# preAutoRoute1.net
KiCad netlist of a schematic drawn in EAGLE
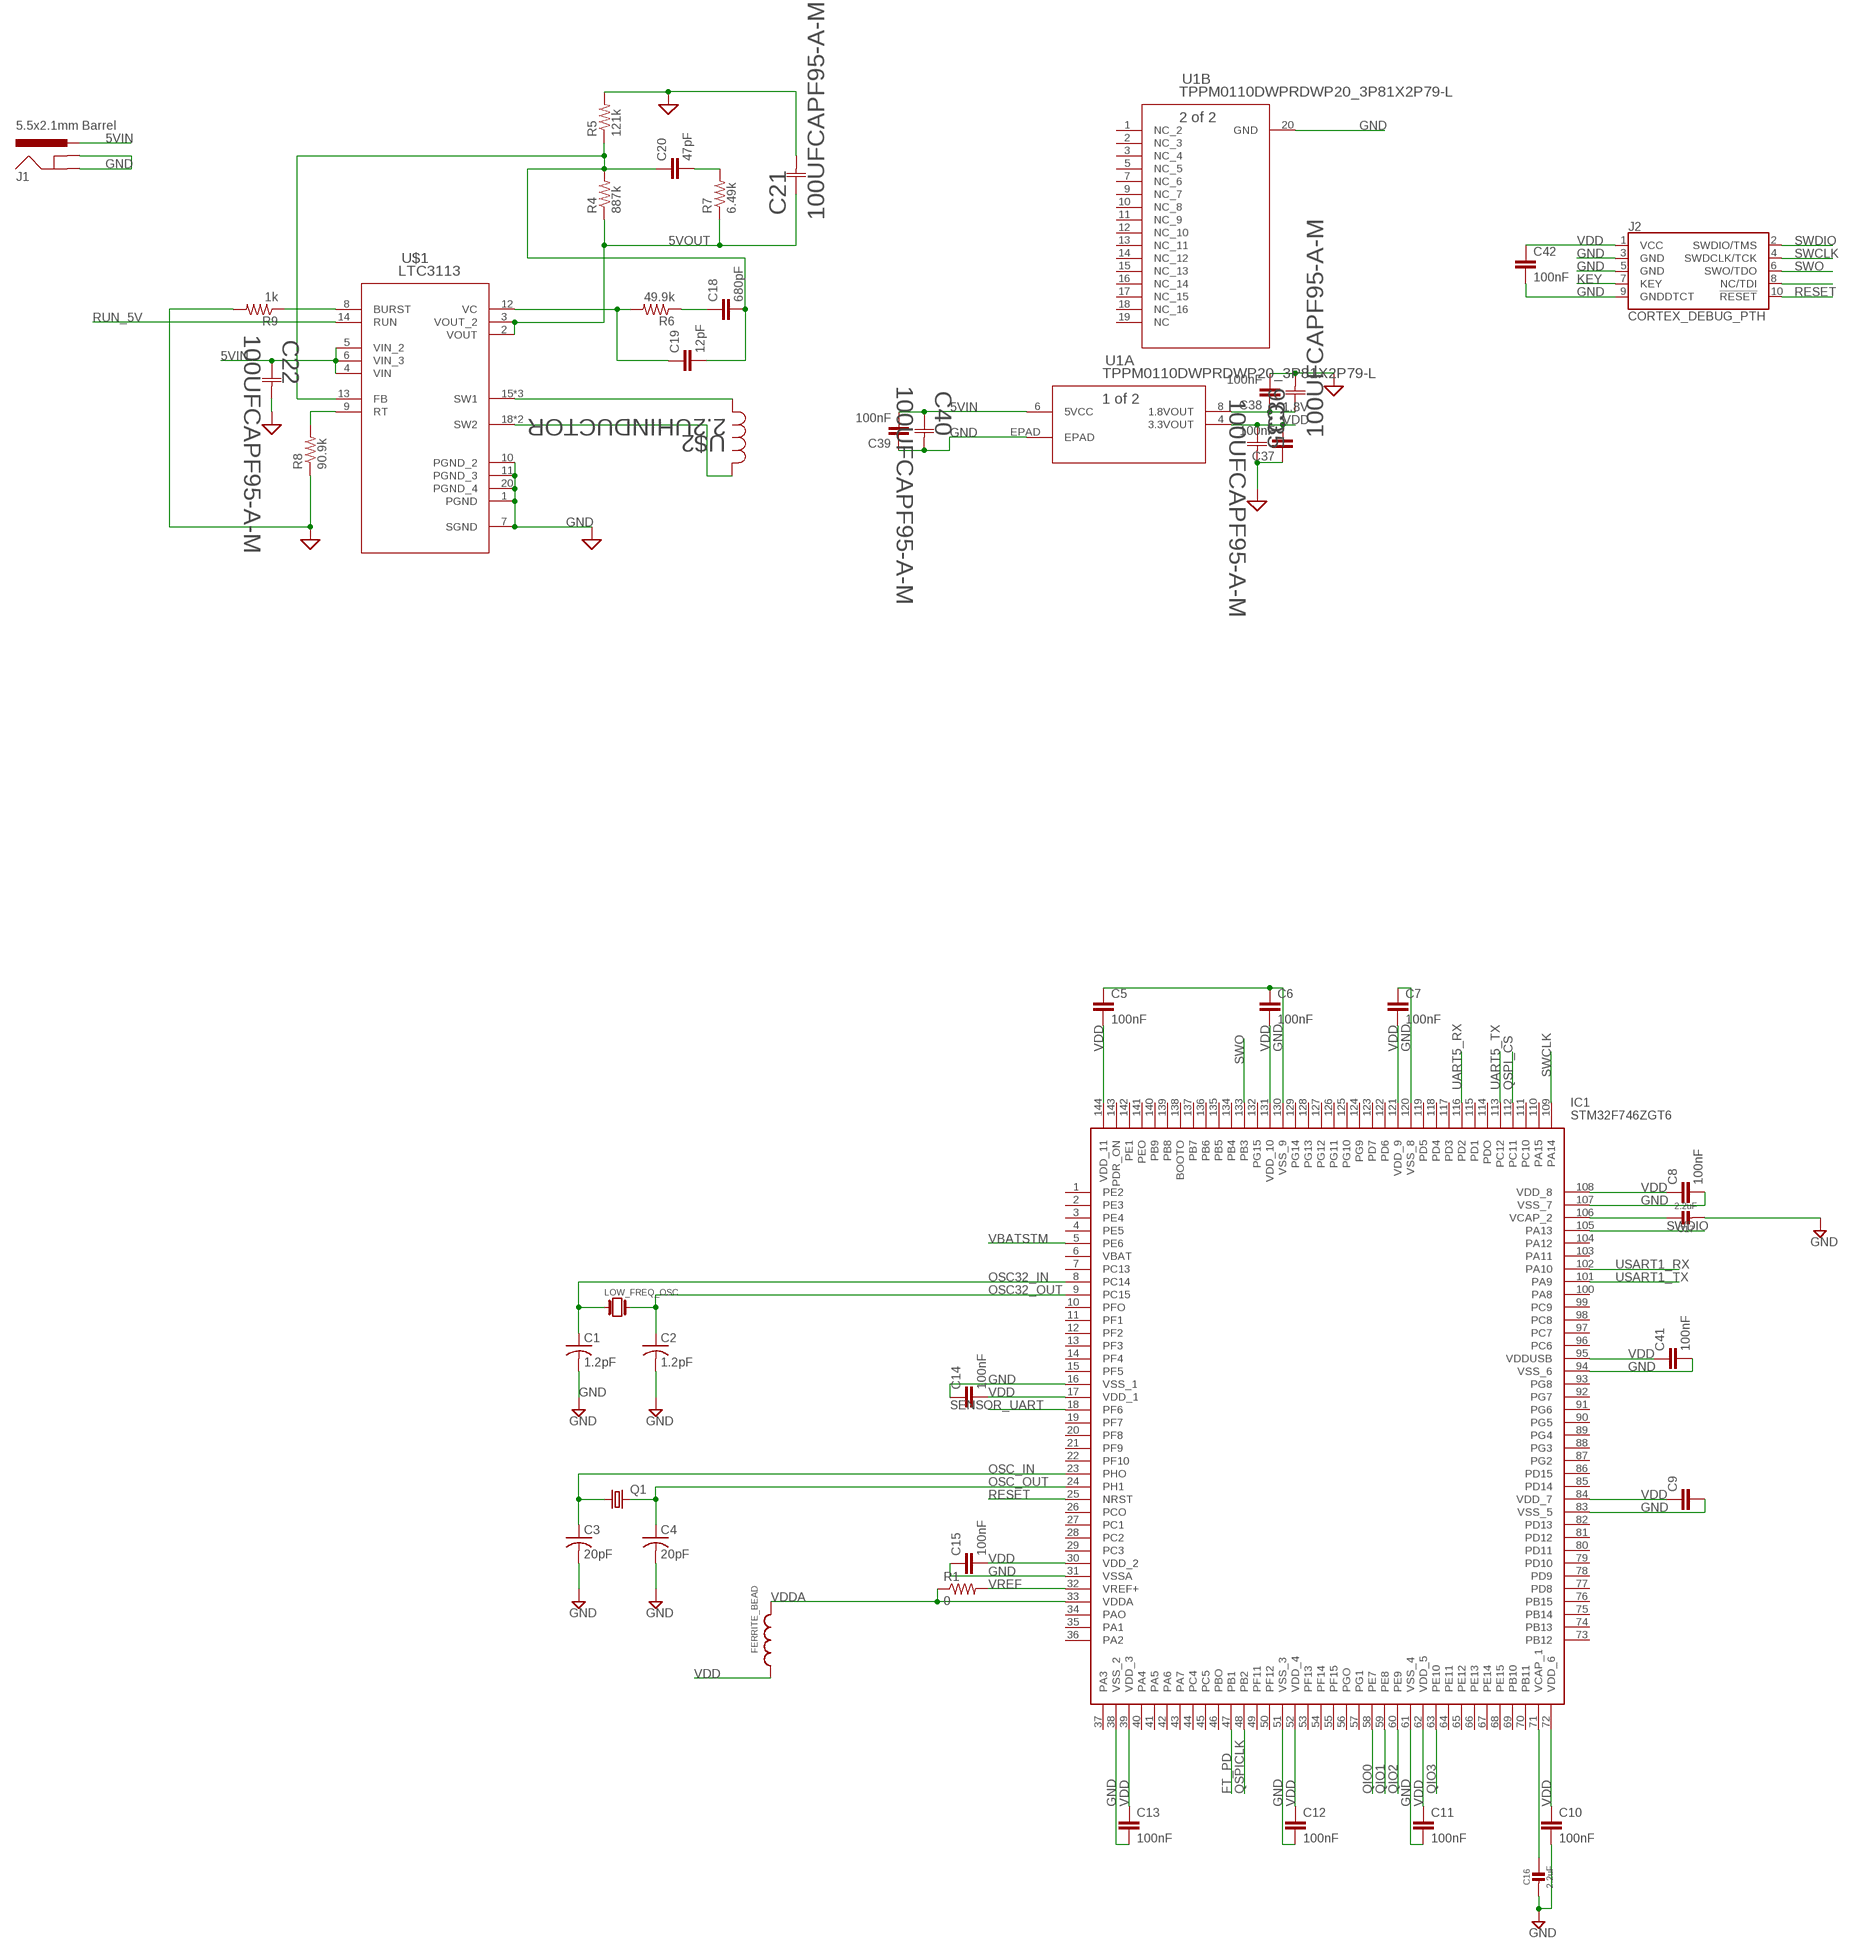
[diagram p0: schematic, sheet 1, part 1 of 2]
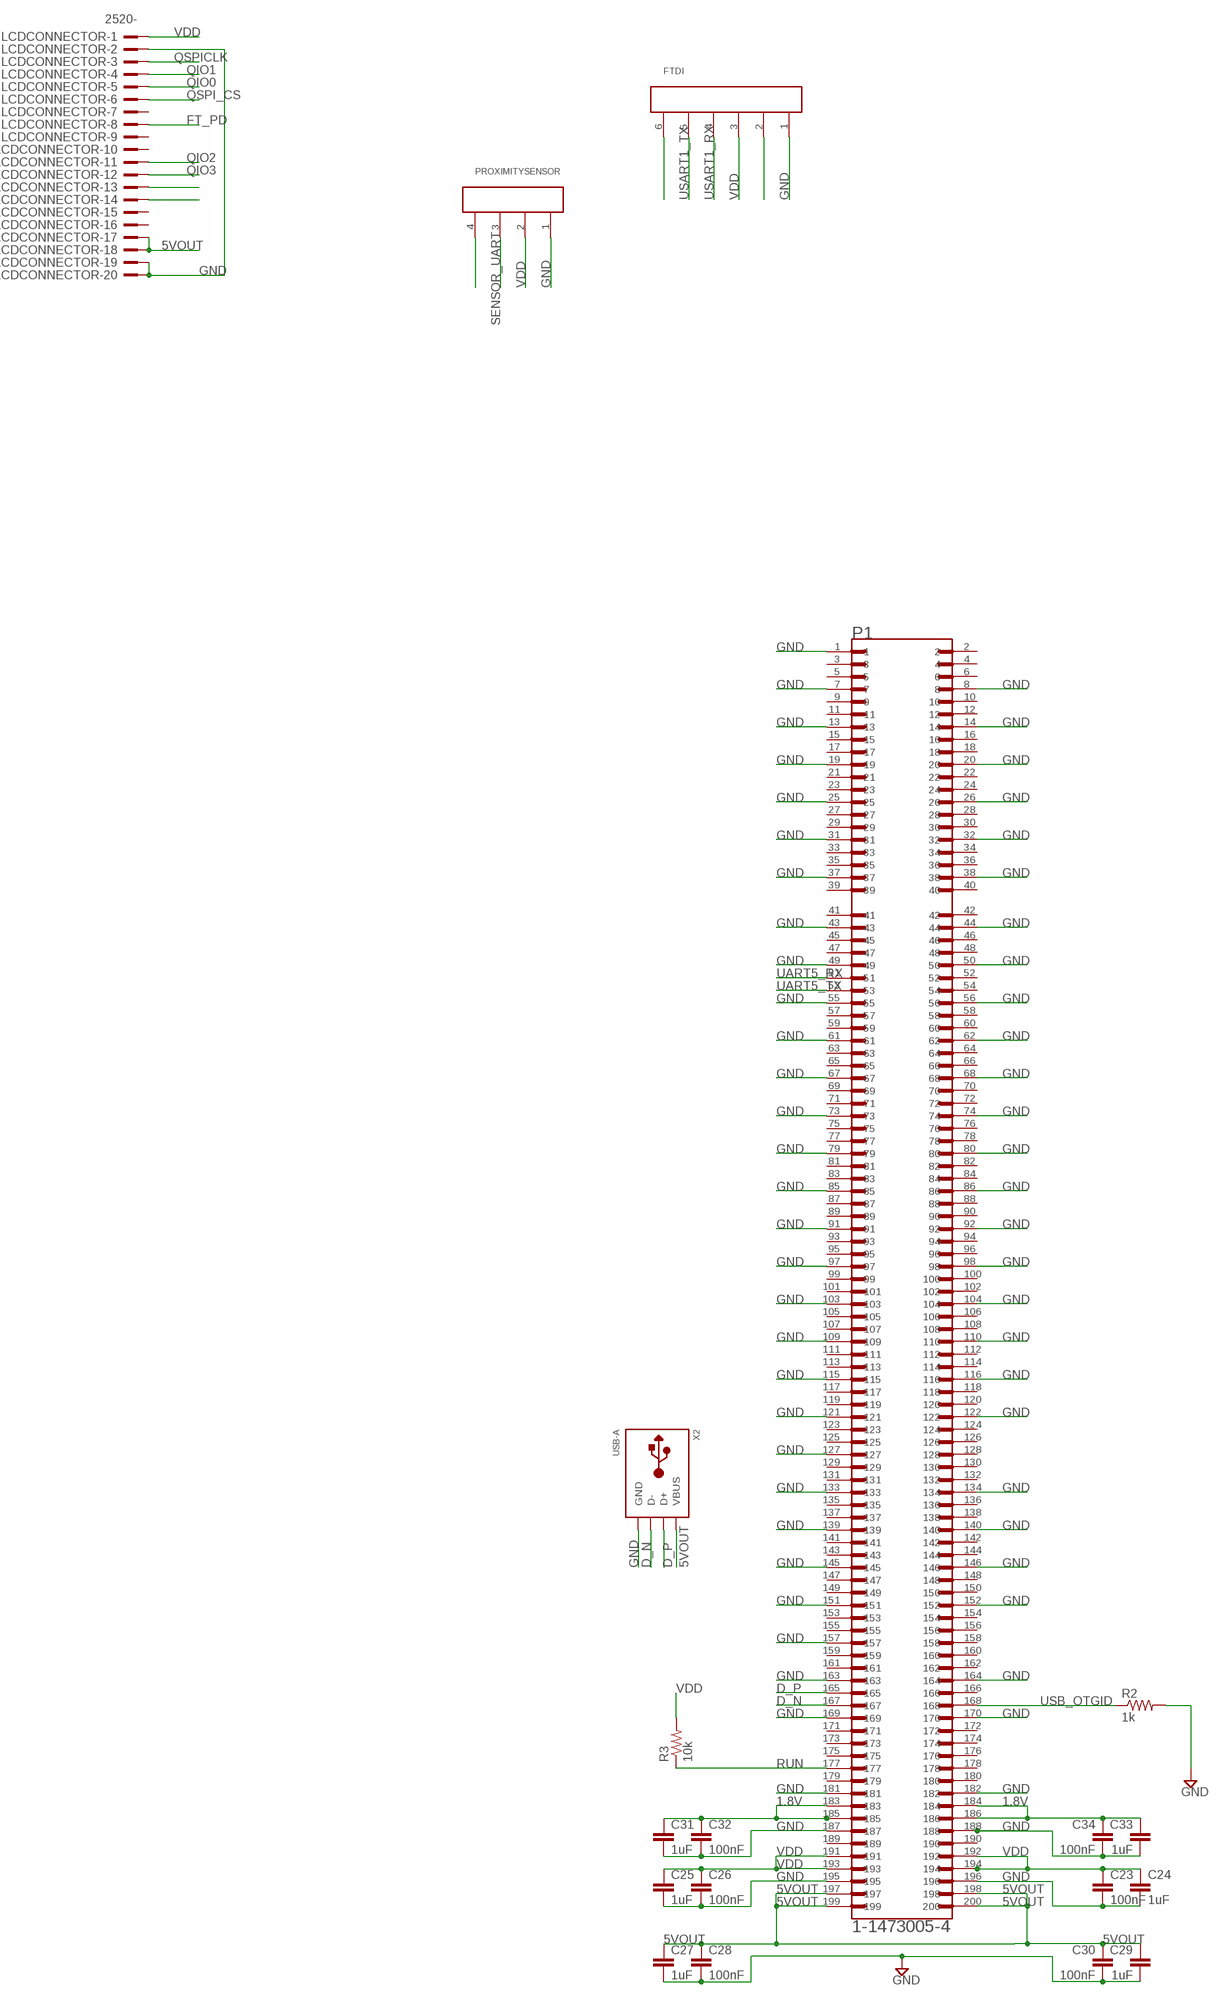
[diagram p1: schematic, sheet 1, part 2 of 2]

(export (version "E")
  (design (tool "Eeschema 10.0.6"))
  (components
    (comp (ref "C1")
      (value "1.2pF")
      (footprint "eagle-import:C0805")
      (libsource (lib "eagle-import") (part "C-USC0805"))
    )
    (comp (ref "C2")
      (value "1.2pF")
      (footprint "eagle-import:C0805")
      (libsource (lib "eagle-import") (part "C-USC0805"))
    )
    (comp (ref "C3")
      (value "20pF")
      (footprint "eagle-import:C0805")
      (libsource (lib "eagle-import") (part "C-USC0805"))
    )
    (comp (ref "C4")
      (value "20pF")
      (footprint "eagle-import:C0805")
      (libsource (lib "eagle-import") (part "C-USC0805"))
    )
    (comp (ref "C5")
      (value "100nF")
      (footprint "eagle-import:C0805")
      (libsource (lib "eagle-import") (part "C-EUC0805"))
    )
    (comp (ref "C6")
      (value "100nF")
      (footprint "eagle-import:C0805")
      (libsource (lib "eagle-import") (part "C-EUC0805"))
    )
    (comp (ref "C7")
      (value "100nF")
      (footprint "eagle-import:C0805")
      (libsource (lib "eagle-import") (part "C-EUC0805"))
    )
    (comp (ref "C8")
      (value "100nF")
      (footprint "eagle-import:C0805")
      (libsource (lib "eagle-import") (part "C-EUC0805"))
    )
    (comp (ref "C9")
      (value "C-EUC0805")
      (footprint "eagle-import:C0805")
      (libsource (lib "eagle-import") (part "C-EUC0805"))
    )
    (comp (ref "C10")
      (value "100nF")
      (footprint "eagle-import:C0805")
      (libsource (lib "eagle-import") (part "C-EUC0805"))
    )
    (comp (ref "C11")
      (value "100nF")
      (footprint "eagle-import:C0805")
      (libsource (lib "eagle-import") (part "C-EUC0805"))
    )
    (comp (ref "C12")
      (value "100nF")
      (footprint "eagle-import:C0805")
      (libsource (lib "eagle-import") (part "C-EUC0805"))
    )
    (comp (ref "C13")
      (value "100nF")
      (footprint "eagle-import:C0805")
      (libsource (lib "eagle-import") (part "C-EUC0805"))
    )
    (comp (ref "C14")
      (value "100nF")
      (footprint "eagle-import:C0805")
      (libsource (lib "eagle-import") (part "C-EUC0805"))
    )
    (comp (ref "C15")
      (value "100nF")
      (footprint "eagle-import:C0805")
      (libsource (lib "eagle-import") (part "C-EUC0805"))
    )
    (comp (ref "C16")
      (value "2.2uF")
      (footprint "eagle-import:0805-NO")
      (libsource (lib "eagle-import") (part "CAP_CERAMIC0805-NOOUTLINE"))
    )
    (comp (ref "C17")
      (value "2.2uF")
      (footprint "eagle-import:0805-NO")
      (libsource (lib "eagle-import") (part "CAP_CERAMIC0805-NOOUTLINE"))
    )
    (comp (ref "C18")
      (value "680pF")
      (footprint "eagle-import:C0805")
      (libsource (lib "eagle-import") (part "C-EUC0805"))
    )
    (comp (ref "C19")
      (value "12pF")
      (footprint "eagle-import:C0805")
      (libsource (lib "eagle-import") (part "C-EUC0805"))
    )
    (comp (ref "C20")
      (value "47pF")
      (footprint "eagle-import:C0805")
      (libsource (lib "eagle-import") (part "C-EUC0805"))
    )
    (comp (ref "C21")
      (value "100UFCAPF95-A-M")
      (footprint "eagle-import:F95-A-M")
      (fields (field (name "MANUFACTURER_PART_NUMBER") "F951A107KAAAQ2"))
      (libsource (lib "eagle-import") (part "100UFCAPF95-A-M"))
    )
    (comp (ref "C22")
      (value "100UFCAPF95-A-M")
      (footprint "eagle-import:F95-A-M")
      (fields (field (name "MANUFACTURER_PART_NUMBER") "F951A107KAAAQ2"))
      (libsource (lib "eagle-import") (part "100UFCAPF95-A-M"))
    )
    (comp (ref "C23")
      (value "100nF")
      (footprint "eagle-import:C0805")
      (libsource (lib "eagle-import") (part "C-EUC0805"))
    )
    (comp (ref "C24")
      (value "1uF")
      (footprint "eagle-import:C0805")
      (libsource (lib "eagle-import") (part "C-EUC0805"))
    )
    (comp (ref "C25")
      (value "1uF")
      (footprint "eagle-import:C0805")
      (libsource (lib "eagle-import") (part "C-EUC0805"))
    )
    (comp (ref "C26")
      (value "100nF")
      (footprint "eagle-import:C0805")
      (libsource (lib "eagle-import") (part "C-EUC0805"))
    )
    (comp (ref "C27")
      (value "1uF")
      (footprint "eagle-import:C0805")
      (libsource (lib "eagle-import") (part "C-EUC0805"))
    )
    (comp (ref "C28")
      (value "100nF")
      (footprint "eagle-import:C0805")
      (libsource (lib "eagle-import") (part "C-EUC0805"))
    )
    (comp (ref "C29")
      (value "1uF")
      (footprint "eagle-import:C0805")
      (libsource (lib "eagle-import") (part "C-EUC0805"))
    )
    (comp (ref "C30")
      (value "100nF")
      (footprint "eagle-import:C0805")
      (libsource (lib "eagle-import") (part "C-EUC0805"))
    )
    (comp (ref "C31")
      (value "1uF")
      (footprint "eagle-import:C0805")
      (libsource (lib "eagle-import") (part "C-EUC0805"))
    )
    (comp (ref "C32")
      (value "100nF")
      (footprint "eagle-import:C0805")
      (libsource (lib "eagle-import") (part "C-EUC0805"))
    )
    (comp (ref "C33")
      (value "1uF")
      (footprint "eagle-import:C0805")
      (libsource (lib "eagle-import") (part "C-EUC0805"))
    )
    (comp (ref "C34")
      (value "100nF")
      (footprint "eagle-import:C0805")
      (libsource (lib "eagle-import") (part "C-EUC0805"))
    )
    (comp (ref "C35")
      (value "100UFCAPF95-A-M")
      (footprint "eagle-import:F95-A-M")
      (fields (field (name "MANUFACTURER_PART_NUMBER") "F951A107KAAAQ2"))
      (libsource (lib "eagle-import") (part "100UFCAPF95-A-M"))
    )
    (comp (ref "C36")
      (value "100UFCAPF95-A-M")
      (footprint "eagle-import:F95-A-M")
      (fields (field (name "MANUFACTURER_PART_NUMBER") "F951A107KAAAQ2"))
      (libsource (lib "eagle-import") (part "100UFCAPF95-A-M"))
    )
    (comp (ref "C37")
      (value "100nF")
      (footprint "eagle-import:C0805")
      (libsource (lib "eagle-import") (part "C-EUC0805"))
    )
    (comp (ref "C38")
      (value "100nF")
      (footprint "eagle-import:C0805")
      (libsource (lib "eagle-import") (part "C-EUC0805"))
    )
    (comp (ref "C39")
      (value "100nF")
      (footprint "eagle-import:C0805")
      (libsource (lib "eagle-import") (part "C-EUC0805"))
    )
    (comp (ref "C40")
      (value "100UFCAPF95-A-M")
      (footprint "eagle-import:F95-A-M")
      (fields (field (name "MANUFACTURER_PART_NUMBER") "F951A107KAAAQ2"))
      (libsource (lib "eagle-import") (part "100UFCAPF95-A-M"))
    )
    (comp (ref "C41")
      (value "100nF")
      (footprint "eagle-import:C0805")
      (libsource (lib "eagle-import") (part "C-EUC0805"))
    )
    (comp (ref "C42")
      (value "100nF")
      (footprint "eagle-import:C0805")
      (libsource (lib "eagle-import") (part "C-EUC0805"))
    )
    (comp (ref "FERRITE_BEAD")
      (value "WE-CBA_0805_782853112_HC")
      (footprint "eagle-import:WE-CBA_0805(W=4)")
      (libsource (lib "eagle-import") (part "WE-CBA_0805_HC_782853112"))
    )
    (comp (ref "FTDI")
      (value "66100611622")
      (footprint "eagle-import:66100611622")
      (libsource (lib "eagle-import") (part "66100611622"))
    )
    (comp (ref "IC1")
      (value "STM32F746ZGT6")
      (footprint "eagle-import:QFP50P2200X2200X160-144N")
      (fields
        (field (name "MOUSER_PART_NUMBER") "511-STM32F746ZGT6")
        (field (name "RS_PART_NUMBER") "8820290")
      )
      (libsource (lib "eagle-import") (part "STM32F746ZGT6"))
    )
    (comp (ref "J1")
      (value "5.5x2.1mm Barrel")
      (footprint "eagle-import:POWER_JACK_SMD")
      (libsource (lib "eagle-import") (part "POWER_JACKSMD"))
    )
    (comp (ref "J2")
      (value "CORTEX_DEBUG_PTH")
      (footprint "eagle-import:2X5-PTH-1.27MM")
      (libsource (lib "eagle-import") (part "CORTEX_DEBUG_PTH"))
    )
    (comp (ref "LCDCONNECTOR")
      (value "2520-")
      (footprint "eagle-import:PAK100_2500-20")
      (libsource (lib "eagle-import") (part "2520-"))
    )
    (comp (ref "LOW_FREQ_OSC")
      (value "GENERIC-CRYSTAL_FC135")
      (footprint "eagle-import:FC135")
      (libsource (lib "eagle-import") (part "GENERIC-CRYSTAL_FC135"))
    )
    (comp (ref "P1")
      (value "1-1473005-4")
      (footprint "eagle-import:TE_1-1473005-4")
      (fields (field (name "MF") "TE Connectivity"))
      (libsource (lib "eagle-import") (part "1-1473005-4"))
    )
    (comp (ref "PROXIMITYSENSOR")
      (value "66100411622")
      (footprint "eagle-import:66100411622")
      (libsource (lib "eagle-import") (part "66100411622"))
    )
    (comp (ref "Q1")
      (value "CRYSTALHC49UP")
      (footprint "eagle-import:HC49UP")
      (libsource (lib "eagle-import") (part "CRYSTALHC49UP"))
    )
    (comp (ref "R1")
      (value "0")
      (footprint "eagle-import:R0805")
      (libsource (lib "eagle-import") (part "R-US_R0805"))
    )
    (comp (ref "R2")
      (value "1k")
      (footprint "eagle-import:R0805")
      (libsource (lib "eagle-import") (part "R-US_R0805"))
    )
    (comp (ref "R3")
      (value "10k")
      (footprint "eagle-import:R0805")
      (libsource (lib "eagle-import") (part "R-US_R0805"))
    )
    (comp (ref "R4")
      (value "887k")
      (footprint "eagle-import:R0805")
      (libsource (lib "eagle-import") (part "resistor_348_R-US_R0805"))
    )
    (comp (ref "R5")
      (value "121k")
      (footprint "eagle-import:R0805")
      (libsource (lib "eagle-import") (part "resistor_348_R-US_R0805"))
    )
    (comp (ref "R6")
      (value "49.9k")
      (footprint "eagle-import:R0805")
      (libsource (lib "eagle-import") (part "resistor_348_R-US_R0805"))
    )
    (comp (ref "R7")
      (value "6.49k")
      (footprint "eagle-import:R0805")
      (libsource (lib "eagle-import") (part "resistor_348_R-US_R0805"))
    )
    (comp (ref "R8")
      (value "90.9k")
      (footprint "eagle-import:R0805")
      (libsource (lib "eagle-import") (part "resistor_348_R-US_R0805"))
    )
    (comp (ref "R9")
      (value "1k")
      (footprint "eagle-import:R0805")
      (libsource (lib "eagle-import") (part "resistor_348_R-US_R0805"))
    )
    (comp (ref "U$1")
      (value "LTC3113")
      (footprint "eagle-import:TSSOP-20_FE_CA")
      (libsource (lib "eagle-import") (part "LTC3113"))
    )
    (comp (ref "U$2")
      (value "2.2UHINDUCTOR")
      (footprint "eagle-import:IND_10040")
      (libsource (lib "eagle-import") (part "2.2UHINDUCTOR"))
    )
    (comp (ref "U1")
      (value "TPPM0110DWPRDWP20_3P81X2P79-L")
      (footprint "eagle-import:DWP20_3P81X2P79-L")
      (fields (field (name "MANUFACTURER_PART_NUMBER") "TPPM0110DWPR"))
      (libsource (lib "eagle-import") (part "TPPM0110DWPRDWP20_3P81X2P79-L"))
    )
    (comp (ref "X2")
      (value "USB-A")
      (footprint "eagle-import:MOLEX_480371000")
      (libsource (lib "eagle-import") (part "USB-A"))
    )
  )
  (nets
    (net (code "1") (name "/1.8V") (class "Default")
      (node (ref "C31") (pin "1") (pinfunction "1_1") (pintype "passive"))
      (node (ref "C32") (pin "1") (pinfunction "1_1") (pintype "passive"))
      (node (ref "C33") (pin "1") (pinfunction "1_1") (pintype "passive"))
      (node (ref "C34") (pin "1") (pinfunction "1_1") (pintype "passive"))
      (node (ref "C36") (pin "1") (pinfunction "1_1") (pintype "passive"))
      (node (ref "C38") (pin "1") (pinfunction "1_1") (pintype "passive"))
      (node (ref "P1") (pin "183") (pinfunction "183_183") (pintype "passive"))
      (node (ref "P1") (pin "184") (pinfunction "184_184") (pintype "passive"))
      (node (ref "P1") (pin "185") (pinfunction "185_185") (pintype "passive"))
      (node (ref "P1") (pin "186") (pinfunction "186_186") (pintype "passive"))
      (node (ref "U1") (pin "8") (pinfunction "1.8VOUT_8") (pintype "output"))
    )
    (net (code "2") (name "/5VIN") (class "Default")
      (node (ref "C22") (pin "1") (pinfunction "1_1") (pintype "passive"))
      (node (ref "C39") (pin "2") (pinfunction "2_2") (pintype "passive"))
      (node (ref "C40") (pin "1") (pinfunction "1_1") (pintype "passive"))
      (node (ref "J1") (pin "VIN0") (pinfunction "PWR_VIN0") (pintype "bidirectional"))
      (node (ref "U$1") (pin "4") (pinfunction "VIN_4") (pintype "passive"))
      (node (ref "U$1") (pin "5") (pinfunction "VIN_2_5") (pintype "passive"))
      (node (ref "U$1") (pin "6") (pinfunction "VIN_3_6") (pintype "passive"))
      (node (ref "U1") (pin "6") (pinfunction "5VCC_6") (pintype "input"))
    )
    (net (code "3") (name "/5VOUT") (class "Default")
      (node (ref "C21") (pin "1") (pinfunction "1_1") (pintype "passive"))
      (node (ref "C27") (pin "1") (pinfunction "1_1") (pintype "passive"))
      (node (ref "C28") (pin "1") (pinfunction "1_1") (pintype "passive"))
      (node (ref "C29") (pin "1") (pinfunction "1_1") (pintype "passive"))
      (node (ref "C30") (pin "1") (pinfunction "1_1") (pintype "passive"))
      (node (ref "LCDCONNECTOR") (pin "17") (pinfunction "KL_17") (pintype "passive"))
      (node (ref "LCDCONNECTOR") (pin "18") (pinfunction "KL_18") (pintype "passive"))
      (node (ref "P1") (pin "197") (pinfunction "197_197") (pintype "passive"))
      (node (ref "P1") (pin "198") (pinfunction "198_198") (pintype "passive"))
      (node (ref "P1") (pin "199") (pinfunction "199_199") (pintype "passive"))
      (node (ref "P1") (pin "200") (pinfunction "200_200") (pintype "passive"))
      (node (ref "R4") (pin "1") (pinfunction "1_1") (pintype "passive"))
      (node (ref "R7") (pin "1") (pinfunction "1_1") (pintype "passive"))
      (node (ref "U$1") (pin "2") (pinfunction "VOUT_2") (pintype "passive"))
      (node (ref "U$1") (pin "3") (pinfunction "VOUT_2_3") (pintype "passive"))
      (node (ref "X2") (pin "1") (pinfunction "VBUS_1") (pintype "power_in"))
    )
    (net (code "4") (name "/D_N") (class "Default")
      (node (ref "P1") (pin "167") (pinfunction "167_167") (pintype "passive"))
      (node (ref "X2") (pin "2") (pinfunction "D-_2") (pintype "bidirectional"))
    )
    (net (code "5") (name "/D_P") (class "Default")
      (node (ref "P1") (pin "165") (pinfunction "165_165") (pintype "passive"))
      (node (ref "X2") (pin "3") (pinfunction "D+_3") (pintype "bidirectional"))
    )
    (net (code "6") (name "/FT_PD") (class "Default")
      (node (ref "IC1") (pin "47") (pinfunction "PB1_47") (pintype "bidirectional"))
      (node (ref "LCDCONNECTOR") (pin "8") (pinfunction "KL_8") (pintype "passive"))
    )
    (net (code "7") (name "/KEY") (class "Default")
      (node (ref "J2") (pin "7") (pinfunction "KEY_7") (pintype "bidirectional"))
    )
    (net (code "8") (name "/OSC32_IN") (class "Default")
      (node (ref "C1") (pin "1") (pinfunction "1_1") (pintype "passive"))
      (node (ref "IC1") (pin "8") (pinfunction "PC14_8") (pintype "bidirectional"))
      (node (ref "LOW_FREQ_OSC") (pin "X1") (pinfunction "1_X1") (pintype "passive"))
    )
    (net (code "9") (name "/OSC32_OUT") (class "Default")
      (node (ref "C2") (pin "1") (pinfunction "1_1") (pintype "passive"))
      (node (ref "IC1") (pin "9") (pinfunction "PC15_9") (pintype "bidirectional"))
      (node (ref "LOW_FREQ_OSC") (pin "X2") (pinfunction "2_X2") (pintype "passive"))
    )
    (net (code "10") (name "/OSC_IN") (class "Default")
      (node (ref "C3") (pin "1") (pinfunction "1_1") (pintype "passive"))
      (node (ref "IC1") (pin "23") (pinfunction "PHO_23") (pintype "bidirectional"))
      (node (ref "Q1") (pin "1") (pinfunction "1_1") (pintype "passive"))
    )
    (net (code "11") (name "/OSC_OUT") (class "Default")
      (node (ref "C4") (pin "1") (pinfunction "1_1") (pintype "passive"))
      (node (ref "IC1") (pin "24") (pinfunction "PH1_24") (pintype "bidirectional"))
      (node (ref "Q1") (pin "2") (pinfunction "2_2") (pintype "passive"))
    )
    (net (code "12") (name "/QIO0") (class "Default")
      (node (ref "IC1") (pin "58") (pinfunction "PE7_58") (pintype "bidirectional"))
      (node (ref "LCDCONNECTOR") (pin "5") (pinfunction "KL_5") (pintype "passive"))
    )
    (net (code "13") (name "/QIO1") (class "Default")
      (node (ref "IC1") (pin "59") (pinfunction "PE8_59") (pintype "bidirectional"))
      (node (ref "LCDCONNECTOR") (pin "4") (pinfunction "KL_4") (pintype "passive"))
    )
    (net (code "14") (name "/QIO2") (class "Default")
      (node (ref "IC1") (pin "60") (pinfunction "PE9_60") (pintype "bidirectional"))
      (node (ref "LCDCONNECTOR") (pin "11") (pinfunction "KL_11") (pintype "passive"))
    )
    (net (code "15") (name "/QIO3") (class "Default")
      (node (ref "IC1") (pin "63") (pinfunction "PE10_63") (pintype "bidirectional"))
      (node (ref "LCDCONNECTOR") (pin "12") (pinfunction "KL_12") (pintype "passive"))
    )
    (net (code "16") (name "/QSPICLK") (class "Default")
      (node (ref "IC1") (pin "48") (pinfunction "PB2_48") (pintype "bidirectional"))
      (node (ref "LCDCONNECTOR") (pin "3") (pinfunction "KL_3") (pintype "passive"))
    )
    (net (code "17") (name "/QSPI_CS") (class "Default")
      (node (ref "IC1") (pin "112") (pinfunction "PC11_112") (pintype "bidirectional"))
      (node (ref "LCDCONNECTOR") (pin "6") (pinfunction "KL_6") (pintype "passive"))
    )
    (net (code "18") (name "/RESET") (class "Default")
      (node (ref "IC1") (pin "25") (pinfunction "NRST_25") (pintype "input"))
      (node (ref "J2") (pin "10") (pinfunction "~{RESET}_10") (pintype "bidirectional"))
    )
    (net (code "19") (name "/RUN") (class "Default")
      (node (ref "P1") (pin "177") (pinfunction "177_177") (pintype "passive"))
      (node (ref "R3") (pin "1") (pinfunction "1_1") (pintype "passive"))
    )
    (net (code "20") (name "/RUN_5V") (class "Default")
      (node (ref "U$1") (pin "14") (pinfunction "RUN_14") (pintype "passive"))
    )
    (net (code "21") (name "/SENSOR_UART") (class "Default")
      (node (ref "IC1") (pin "18") (pinfunction "PF6_18") (pintype "bidirectional"))
      (node (ref "PROXIMITYSENSOR") (pin "3") (pinfunction "3_3") (pintype "passive"))
    )
    (net (code "22") (name "/SWCLK") (class "Default")
      (node (ref "IC1") (pin "109") (pinfunction "PA14_109") (pintype "bidirectional"))
      (node (ref "J2") (pin "4") (pinfunction "SWDCLK/TCK_4") (pintype "bidirectional"))
    )
    (net (code "23") (name "/SWDIO") (class "Default")
      (node (ref "IC1") (pin "105") (pinfunction "PA13_105") (pintype "bidirectional"))
      (node (ref "J2") (pin "2") (pinfunction "SWDIO/TMS_2") (pintype "bidirectional"))
    )
    (net (code "24") (name "/SWO") (class "Default")
      (node (ref "IC1") (pin "133") (pinfunction "PB3_133") (pintype "bidirectional"))
      (node (ref "J2") (pin "6") (pinfunction "SWO/TDO_6") (pintype "bidirectional"))
    )
    (net (code "25") (name "/UART5_RX") (class "Default")
      (node (ref "IC1") (pin "116") (pinfunction "PD2_116") (pintype "bidirectional"))
      (node (ref "P1") (pin "51") (pinfunction "51_51") (pintype "passive"))
    )
    (net (code "26") (name "/UART5_TX") (class "Default")
      (node (ref "IC1") (pin "113") (pinfunction "PC12_113") (pintype "bidirectional"))
      (node (ref "P1") (pin "53") (pinfunction "53_53") (pintype "passive"))
    )
    (net (code "27") (name "/USART1_RX") (class "Default")
      (node (ref "FTDI") (pin "4") (pinfunction "4_4") (pintype "passive"))
      (node (ref "IC1") (pin "102") (pinfunction "PA10_102") (pintype "bidirectional"))
    )
    (net (code "28") (name "/USART1_TX") (class "Default")
      (node (ref "FTDI") (pin "5") (pinfunction "5_5") (pintype "passive"))
      (node (ref "IC1") (pin "101") (pinfunction "PA9_101") (pintype "bidirectional"))
    )
    (net (code "29") (name "/USB_OTGID") (class "Default")
      (node (ref "P1") (pin "168") (pinfunction "168_168") (pintype "passive"))
      (node (ref "R2") (pin "1") (pinfunction "1_1") (pintype "passive"))
    )
    (net (code "30") (name "/VBATSTM") (class "Default")
      (node (ref "IC1") (pin "5") (pinfunction "PE6_5") (pintype "bidirectional"))
    )
    (net (code "31") (name "/VDD") (class "Default")
      (node (ref "C10") (pin "1") (pinfunction "1_1") (pintype "passive"))
      (node (ref "C11") (pin "1") (pinfunction "1_1") (pintype "passive"))
      (node (ref "C12") (pin "1") (pinfunction "1_1") (pintype "passive"))
      (node (ref "C13") (pin "1") (pinfunction "1_1") (pintype "passive"))
      (node (ref "C14") (pin "2") (pinfunction "2_2") (pintype "passive"))
      (node (ref "C15") (pin "2") (pinfunction "2_2") (pintype "passive"))
      (node (ref "C23") (pin "1") (pinfunction "1_1") (pintype "passive"))
      (node (ref "C24") (pin "1") (pinfunction "1_1") (pintype "passive"))
      (node (ref "C25") (pin "1") (pinfunction "1_1") (pintype "passive"))
      (node (ref "C26") (pin "1") (pinfunction "1_1") (pintype "passive"))
      (node (ref "C35") (pin "1") (pinfunction "1_1") (pintype "passive"))
      (node (ref "C37") (pin "2") (pinfunction "2_2") (pintype "passive"))
      (node (ref "C41") (pin "1") (pinfunction "1_1") (pintype "passive"))
      (node (ref "C42") (pin "1") (pinfunction "1_1") (pintype "passive"))
      (node (ref "C5") (pin "2") (pinfunction "2_2") (pintype "passive"))
      (node (ref "C6") (pin "2") (pinfunction "2_2") (pintype "passive"))
      (node (ref "C7") (pin "2") (pinfunction "2_2") (pintype "passive"))
      (node (ref "C8") (pin "1") (pinfunction "1_1") (pintype "passive"))
      (node (ref "C9") (pin "1") (pinfunction "1_1") (pintype "passive"))
      (node (ref "FERRITE_BEAD") (pin "1") (pinfunction "1_1") (pintype "passive"))
      (node (ref "FTDI") (pin "3") (pinfunction "3_3") (pintype "passive"))
      (node (ref "IC1") (pin "108") (pinfunction "VDD_8_108") (pintype "power_in"))
      (node (ref "IC1") (pin "121") (pinfunction "VDD_9_121") (pintype "power_in"))
      (node (ref "IC1") (pin "131") (pinfunction "VDD_10_131") (pintype "power_in"))
      (node (ref "IC1") (pin "144") (pinfunction "VDD_11_144") (pintype "power_in"))
      (node (ref "IC1") (pin "17") (pinfunction "VDD_1_17") (pintype "power_in"))
      (node (ref "IC1") (pin "30") (pinfunction "VDD_2_30") (pintype "power_in"))
      (node (ref "IC1") (pin "39") (pinfunction "VDD_3_39") (pintype "power_in"))
      (node (ref "IC1") (pin "52") (pinfunction "VDD_4_52") (pintype "power_in"))
      (node (ref "IC1") (pin "62") (pinfunction "VDD_5_62") (pintype "power_in"))
      (node (ref "IC1") (pin "72") (pinfunction "VDD_6_72") (pintype "power_in"))
      (node (ref "IC1") (pin "84") (pinfunction "VDD_7_84") (pintype "power_in"))
      (node (ref "IC1") (pin "95") (pinfunction "VDDUSB_95") (pintype "power_in"))
      (node (ref "J2") (pin "1") (pinfunction "VCC_1") (pintype "bidirectional"))
      (node (ref "LCDCONNECTOR") (pin "1") (pinfunction "KL_1") (pintype "passive"))
      (node (ref "P1") (pin "191") (pinfunction "191_191") (pintype "passive"))
      (node (ref "P1") (pin "192") (pinfunction "192_192") (pintype "passive"))
      (node (ref "P1") (pin "193") (pinfunction "193_193") (pintype "passive"))
      (node (ref "P1") (pin "194") (pinfunction "194_194") (pintype "passive"))
      (node (ref "PROXIMITYSENSOR") (pin "2") (pinfunction "2_2") (pintype "passive"))
      (node (ref "R3") (pin "2") (pinfunction "2_2") (pintype "passive"))
      (node (ref "U1") (pin "4") (pinfunction "3.3VOUT_4") (pintype "output"))
    )
    (net (code "32") (name "/VDDA") (class "Default")
      (node (ref "FERRITE_BEAD") (pin "2") (pinfunction "2_2") (pintype "passive"))
      (node (ref "IC1") (pin "33") (pinfunction "VDDA_33") (pintype "power_in"))
      (node (ref "R1") (pin "1") (pinfunction "1_1") (pintype "passive"))
    )
    (net (code "33") (name "/VREF") (class "Default")
      (node (ref "IC1") (pin "32") (pinfunction "VREF+_32") (pintype "input"))
      (node (ref "R1") (pin "2") (pinfunction "2_2") (pintype "passive"))
    )
    (net (code "34") (name "GND") (class "Default")
      (node (ref "C1") (pin "2") (pinfunction "2_2") (pintype "passive"))
      (node (ref "C10") (pin "2") (pinfunction "2_2") (pintype "passive"))
      (node (ref "C11") (pin "2") (pinfunction "2_2") (pintype "passive"))
      (node (ref "C12") (pin "2") (pinfunction "2_2") (pintype "passive"))
      (node (ref "C13") (pin "2") (pinfunction "2_2") (pintype "passive"))
      (node (ref "C14") (pin "1") (pinfunction "1_1") (pintype "passive"))
      (node (ref "C15") (pin "1") (pinfunction "1_1") (pintype "passive"))
      (node (ref "C16") (pin "2") (pinfunction "2_2") (pintype "passive"))
      (node (ref "C17") (pin "2") (pinfunction "2_2") (pintype "passive"))
      (node (ref "C2") (pin "2") (pinfunction "2_2") (pintype "passive"))
      (node (ref "C21") (pin "2") (pinfunction "2_2") (pintype "passive"))
      (node (ref "C22") (pin "2") (pinfunction "2_2") (pintype "passive"))
      (node (ref "C23") (pin "2") (pinfunction "2_2") (pintype "passive"))
      (node (ref "C24") (pin "2") (pinfunction "2_2") (pintype "passive"))
      (node (ref "C25") (pin "2") (pinfunction "2_2") (pintype "passive"))
      (node (ref "C26") (pin "2") (pinfunction "2_2") (pintype "passive"))
      (node (ref "C27") (pin "2") (pinfunction "2_2") (pintype "passive"))
      (node (ref "C28") (pin "2") (pinfunction "2_2") (pintype "passive"))
      (node (ref "C29") (pin "2") (pinfunction "2_2") (pintype "passive"))
      (node (ref "C3") (pin "2") (pinfunction "2_2") (pintype "passive"))
      (node (ref "C30") (pin "2") (pinfunction "2_2") (pintype "passive"))
      (node (ref "C31") (pin "2") (pinfunction "2_2") (pintype "passive"))
      (node (ref "C32") (pin "2") (pinfunction "2_2") (pintype "passive"))
      (node (ref "C33") (pin "2") (pinfunction "2_2") (pintype "passive"))
      (node (ref "C34") (pin "2") (pinfunction "2_2") (pintype "passive"))
      (node (ref "C35") (pin "2") (pinfunction "2_2") (pintype "passive"))
      (node (ref "C36") (pin "2") (pinfunction "2_2") (pintype "passive"))
      (node (ref "C37") (pin "1") (pinfunction "1_1") (pintype "passive"))
      (node (ref "C38") (pin "2") (pinfunction "2_2") (pintype "passive"))
      (node (ref "C39") (pin "1") (pinfunction "1_1") (pintype "passive"))
      (node (ref "C4") (pin "2") (pinfunction "2_2") (pintype "passive"))
      (node (ref "C40") (pin "2") (pinfunction "2_2") (pintype "passive"))
      (node (ref "C41") (pin "2") (pinfunction "2_2") (pintype "passive"))
      (node (ref "C42") (pin "2") (pinfunction "2_2") (pintype "passive"))
      (node (ref "C5") (pin "1") (pinfunction "1_1") (pintype "passive"))
      (node (ref "C6") (pin "1") (pinfunction "1_1") (pintype "passive"))
      (node (ref "C7") (pin "1") (pinfunction "1_1") (pintype "passive"))
      (node (ref "C8") (pin "2") (pinfunction "2_2") (pintype "passive"))
      (node (ref "C9") (pin "2") (pinfunction "2_2") (pintype "passive"))
      (node (ref "FTDI") (pin "1") (pinfunction "1_1") (pintype "passive"))
      (node (ref "IC1") (pin "107") (pinfunction "VSS_7_107") (pintype "power_in"))
      (node (ref "IC1") (pin "120") (pinfunction "VSS_8_120") (pintype "power_in"))
      (node (ref "IC1") (pin "130") (pinfunction "VSS_9_130") (pintype "power_in"))
      (node (ref "IC1") (pin "16") (pinfunction "VSS_1_16") (pintype "power_in"))
      (node (ref "IC1") (pin "31") (pinfunction "VSSA_31") (pintype "power_in"))
      (node (ref "IC1") (pin "38") (pinfunction "VSS_2_38") (pintype "power_in"))
      (node (ref "IC1") (pin "51") (pinfunction "VSS_3_51") (pintype "power_in"))
      (node (ref "IC1") (pin "61") (pinfunction "VSS_4_61") (pintype "power_in"))
      (node (ref "IC1") (pin "83") (pinfunction "VSS_5_83") (pintype "power_in"))
      (node (ref "IC1") (pin "94") (pinfunction "VSS_6_94") (pintype "power_in"))
      (node (ref "J1") (pin "GND") (pinfunction "GNDBREAK_GND") (pintype "bidirectional"))
      (node (ref "J1") (pin "P$4") (pinfunction "GND_P$4") (pintype "bidirectional"))
      (node (ref "J2") (pin "3") (pinfunction "GND_3") (pintype "bidirectional"))
      (node (ref "J2") (pin "5") (pinfunction "GND_5") (pintype "bidirectional"))
      (node (ref "J2") (pin "9") (pinfunction "GNDDTCT_9") (pintype "bidirectional"))
      (node (ref "LCDCONNECTOR") (pin "19") (pinfunction "KL_19") (pintype "passive"))
      (node (ref "LCDCONNECTOR") (pin "2") (pinfunction "KL_2") (pintype "passive"))
      (node (ref "LCDCONNECTOR") (pin "20") (pinfunction "KL_20") (pintype "passive"))
      (node (ref "P1") (pin "1") (pinfunction "1_1") (pintype "passive"))
      (node (ref "P1") (pin "103") (pinfunction "103_103") (pintype "passive"))
      (node (ref "P1") (pin "104") (pinfunction "104_104") (pintype "passive"))
      (node (ref "P1") (pin "109") (pinfunction "109_109") (pintype "passive"))
      (node (ref "P1") (pin "110") (pinfunction "110_110") (pintype "passive"))
      (node (ref "P1") (pin "115") (pinfunction "115_115") (pintype "passive"))
      (node (ref "P1") (pin "116") (pinfunction "116_116") (pintype "passive"))
      (node (ref "P1") (pin "121") (pinfunction "121_121") (pintype "passive"))
      (node (ref "P1") (pin "122") (pinfunction "122_122") (pintype "passive"))
      (node (ref "P1") (pin "127") (pinfunction "127_127") (pintype "passive"))
      (node (ref "P1") (pin "13") (pinfunction "13_13") (pintype "passive"))
      (node (ref "P1") (pin "133") (pinfunction "133_133") (pintype "passive"))
      (node (ref "P1") (pin "134") (pinfunction "134_134") (pintype "passive"))
      (node (ref "P1") (pin "139") (pinfunction "139_139") (pintype "passive"))
      (node (ref "P1") (pin "14") (pinfunction "14_14") (pintype "passive"))
      (node (ref "P1") (pin "140") (pinfunction "140_140") (pintype "passive"))
      (node (ref "P1") (pin "145") (pinfunction "145_145") (pintype "passive"))
      (node (ref "P1") (pin "146") (pinfunction "146_146") (pintype "passive"))
      (node (ref "P1") (pin "151") (pinfunction "151_151") (pintype "passive"))
      (node (ref "P1") (pin "152") (pinfunction "152_152") (pintype "passive"))
      (node (ref "P1") (pin "157") (pinfunction "157_157") (pintype "passive"))
      (node (ref "P1") (pin "163") (pinfunction "163_163") (pintype "passive"))
      (node (ref "P1") (pin "164") (pinfunction "164_164") (pintype "passive"))
      (node (ref "P1") (pin "169") (pinfunction "169_169") (pintype "passive"))
      (node (ref "P1") (pin "170") (pinfunction "170_170") (pintype "passive"))
      (node (ref "P1") (pin "181") (pinfunction "181_181") (pintype "passive"))
      (node (ref "P1") (pin "182") (pinfunction "182_182") (pintype "passive"))
      (node (ref "P1") (pin "187") (pinfunction "187_187") (pintype "passive"))
      (node (ref "P1") (pin "188") (pinfunction "188_188") (pintype "passive"))
      (node (ref "P1") (pin "19") (pinfunction "19_19") (pintype "passive"))
      (node (ref "P1") (pin "195") (pinfunction "195_195") (pintype "passive"))
      (node (ref "P1") (pin "196") (pinfunction "196_196") (pintype "passive"))
      (node (ref "P1") (pin "20") (pinfunction "20_20") (pintype "passive"))
      (node (ref "P1") (pin "25") (pinfunction "25_25") (pintype "passive"))
      (node (ref "P1") (pin "26") (pinfunction "26_26") (pintype "passive"))
      (node (ref "P1") (pin "31") (pinfunction "31_31") (pintype "passive"))
      (node (ref "P1") (pin "32") (pinfunction "32_32") (pintype "passive"))
      (node (ref "P1") (pin "37") (pinfunction "37_37") (pintype "passive"))
      (node (ref "P1") (pin "38") (pinfunction "38_38") (pintype "passive"))
      (node (ref "P1") (pin "43") (pinfunction "43_43") (pintype "passive"))
      (node (ref "P1") (pin "44") (pinfunction "44_44") (pintype "passive"))
      (node (ref "P1") (pin "49") (pinfunction "49_49") (pintype "passive"))
      (node (ref "P1") (pin "50") (pinfunction "50_50") (pintype "passive"))
      (node (ref "P1") (pin "55") (pinfunction "55_55") (pintype "passive"))
      (node (ref "P1") (pin "56") (pinfunction "56_56") (pintype "passive"))
      (node (ref "P1") (pin "61") (pinfunction "61_61") (pintype "passive"))
      (node (ref "P1") (pin "62") (pinfunction "62_62") (pintype "passive"))
      (node (ref "P1") (pin "67") (pinfunction "67_67") (pintype "passive"))
      (node (ref "P1") (pin "68") (pinfunction "68_68") (pintype "passive"))
      (node (ref "P1") (pin "7") (pinfunction "7_7") (pintype "passive"))
      (node (ref "P1") (pin "73") (pinfunction "73_73") (pintype "passive"))
      (node (ref "P1") (pin "74") (pinfunction "74_74") (pintype "passive"))
      (node (ref "P1") (pin "79") (pinfunction "79_79") (pintype "passive"))
      (node (ref "P1") (pin "8") (pinfunction "8_8") (pintype "passive"))
      (node (ref "P1") (pin "80") (pinfunction "80_80") (pintype "passive"))
      (node (ref "P1") (pin "85") (pinfunction "85_85") (pintype "passive"))
      (node (ref "P1") (pin "86") (pinfunction "86_86") (pintype "passive"))
      (node (ref "P1") (pin "91") (pinfunction "91_91") (pintype "passive"))
      (node (ref "P1") (pin "92") (pinfunction "92_92") (pintype "passive"))
      (node (ref "P1") (pin "97") (pinfunction "97_97") (pintype "passive"))
      (node (ref "P1") (pin "98") (pinfunction "98_98") (pintype "passive"))
      (node (ref "PROXIMITYSENSOR") (pin "1") (pinfunction "1_1") (pintype "passive"))
      (node (ref "R2") (pin "2") (pinfunction "2_2") (pintype "passive"))
      (node (ref "R5") (pin "2") (pinfunction "2_2") (pintype "passive"))
      (node (ref "R8") (pin "1") (pinfunction "1_1") (pintype "passive"))
      (node (ref "R9") (pin "2") (pinfunction "2_2") (pintype "passive"))
      (node (ref "U$1") (pin "1") (pinfunction "PGND_1") (pintype "passive"))
      (node (ref "U$1") (pin "10") (pinfunction "PGND_2_10") (pintype "passive"))
      (node (ref "U$1") (pin "11") (pinfunction "PGND_3_11") (pintype "passive"))
      (node (ref "U$1") (pin "20") (pinfunction "PGND_4_20") (pintype "passive"))
      (node (ref "U$1") (pin "7") (pinfunction "SGND_7") (pintype "passive"))
      (node (ref "U1") (pin "20") (pinfunction "GND_20") (pintype "power_in"))
      (node (ref "U1") (pin "EPAD") (pinfunction "EPAD_EPAD") (pintype "passive"))
      (node (ref "X2") (pin "4") (pinfunction "GND_4") (pintype "power_in"))
    )
    (net (code "35") (name "Net-(C18-Pad1)") (class "Default")
      (node (ref "C18") (pin "1") (pinfunction "1_1") (pintype "passive"))
      (node (ref "R6") (pin "1") (pinfunction "1_1") (pintype "passive"))
    )
    (net (code "36") (name "Net-(C20-Pad2)") (class "Default")
      (node (ref "C20") (pin "2") (pinfunction "2_2") (pintype "passive"))
      (node (ref "R7") (pin "2") (pinfunction "2_2") (pintype "passive"))
    )
    (net (code "37") (name "Net-(IC1-VCAP_1)") (class "Default")
      (node (ref "C16") (pin "1") (pinfunction "1_1") (pintype "passive"))
      (node (ref "IC1") (pin "71") (pinfunction "VCAP_1_71") (pintype "bidirectional"))
    )
    (net (code "38") (name "Net-(IC1-VCAP_2)") (class "Default")
      (node (ref "C17") (pin "1") (pinfunction "1_1") (pintype "passive"))
      (node (ref "IC1") (pin "106") (pinfunction "VCAP_2_106") (pintype "bidirectional"))
    )
    (net (code "39") (name "Net-(U$1-BURST)") (class "Default")
      (node (ref "R9") (pin "1") (pinfunction "1_1") (pintype "passive"))
      (node (ref "U$1") (pin "8") (pinfunction "BURST_8") (pintype "passive"))
    )
    (net (code "40") (name "Net-(U$1-FB)") (class "Default")
      (node (ref "C18") (pin "2") (pinfunction "2_2") (pintype "passive"))
      (node (ref "C19") (pin "2") (pinfunction "2_2") (pintype "passive"))
      (node (ref "C20") (pin "1") (pinfunction "1_1") (pintype "passive"))
      (node (ref "R4") (pin "2") (pinfunction "2_2") (pintype "passive"))
      (node (ref "R5") (pin "1") (pinfunction "1_1") (pintype "passive"))
      (node (ref "U$1") (pin "13") (pinfunction "FB_13") (pintype "passive"))
    )
    (net (code "41") (name "Net-(U$1-RT)") (class "Default")
      (node (ref "R8") (pin "2") (pinfunction "2_2") (pintype "passive"))
      (node (ref "U$1") (pin "9") (pinfunction "RT_9") (pintype "passive"))
    )
    (net (code "42") (name "Net-(U$1-SW1-Pad15)") (class "Default")
      (node (ref "U$1") (pin "15") (pinfunction "SW1_15") (pintype "passive"))
      (node (ref "U$1") (pin "16") (pinfunction "SW1_16") (pintype "passive"))
      (node (ref "U$1") (pin "17") (pinfunction "SW1_17") (pintype "passive"))
      (node (ref "U$2") (pin "2") (pinfunction "2_2") (pintype "passive"))
    )
    (net (code "43") (name "Net-(U$1-SW2-Pad18)") (class "Default")
      (node (ref "U$1") (pin "18") (pinfunction "SW2_18") (pintype "passive"))
      (node (ref "U$1") (pin "19") (pinfunction "SW2_19") (pintype "passive"))
      (node (ref "U$2") (pin "1") (pinfunction "1_1") (pintype "passive"))
    )
    (net (code "44") (name "Net-(U$1-VC)") (class "Default")
      (node (ref "C19") (pin "1") (pinfunction "1_1") (pintype "passive"))
      (node (ref "R6") (pin "2") (pinfunction "2_2") (pintype "passive"))
      (node (ref "U$1") (pin "12") (pinfunction "VC_12") (pintype "passive"))
    )
    (net (code "45") (name "unconnected-(FTDI-Pad2)") (class "Default")
      (node (ref "FTDI") (pin "2") (pinfunction "2_2") (pintype "passive"))
    )
    (net (code "46") (name "unconnected-(FTDI-Pad6)") (class "Default")
      (node (ref "FTDI") (pin "6") (pinfunction "6_6") (pintype "passive"))
    )
    (net (code "47") (name "unconnected-(IC1-BOOTO-Pad138)") (class "Default")
      (node (ref "IC1") (pin "138") (pinfunction "BOOTO_138") (pintype "bidirectional"))
    )
    (net (code "48") (name "unconnected-(IC1-PA1-Pad35)") (class "Default")
      (node (ref "IC1") (pin "35") (pinfunction "PA1_35") (pintype "bidirectional"))
    )
    (net (code "49") (name "unconnected-(IC1-PA2-Pad36)") (class "Default")
      (node (ref "IC1") (pin "36") (pinfunction "PA2_36") (pintype "bidirectional"))
    )
    (net (code "50") (name "unconnected-(IC1-PA3-Pad37)") (class "Default")
      (node (ref "IC1") (pin "37") (pinfunction "PA3_37") (pintype "bidirectional"))
    )
    (net (code "51") (name "unconnected-(IC1-PA4-Pad40)") (class "Default")
      (node (ref "IC1") (pin "40") (pinfunction "PA4_40") (pintype "bidirectional"))
    )
    (net (code "52") (name "unconnected-(IC1-PA5-Pad41)") (class "Default")
      (node (ref "IC1") (pin "41") (pinfunction "PA5_41") (pintype "bidirectional"))
    )
    (net (code "53") (name "unconnected-(IC1-PA6-Pad42)") (class "Default")
      (node (ref "IC1") (pin "42") (pinfunction "PA6_42") (pintype "bidirectional"))
    )
    (net (code "54") (name "unconnected-(IC1-PA7-Pad43)") (class "Default")
      (node (ref "IC1") (pin "43") (pinfunction "PA7_43") (pintype "bidirectional"))
    )
    (net (code "55") (name "unconnected-(IC1-PA8-Pad100)") (class "Default")
      (node (ref "IC1") (pin "100") (pinfunction "PA8_100") (pintype "bidirectional"))
    )
    (net (code "56") (name "unconnected-(IC1-PA11-Pad103)") (class "Default")
      (node (ref "IC1") (pin "103") (pinfunction "PA11_103") (pintype "bidirectional"))
    )
    (net (code "57") (name "unconnected-(IC1-PA12-Pad104)") (class "Default")
      (node (ref "IC1") (pin "104") (pinfunction "PA12_104") (pintype "bidirectional"))
    )
    (net (code "58") (name "unconnected-(IC1-PA15-Pad110)") (class "Default")
      (node (ref "IC1") (pin "110") (pinfunction "PA15_110") (pintype "bidirectional"))
    )
    (net (code "59") (name "unconnected-(IC1-PAO-Pad34)") (class "Default")
      (node (ref "IC1") (pin "34") (pinfunction "PAO_34") (pintype "bidirectional"))
    )
    (net (code "60") (name "unconnected-(IC1-PB4-Pad134)") (class "Default")
      (node (ref "IC1") (pin "134") (pinfunction "PB4_134") (pintype "bidirectional"))
    )
    (net (code "61") (name "unconnected-(IC1-PB5-Pad135)") (class "Default")
      (node (ref "IC1") (pin "135") (pinfunction "PB5_135") (pintype "bidirectional"))
    )
    (net (code "62") (name "unconnected-(IC1-PB6-Pad136)") (class "Default")
      (node (ref "IC1") (pin "136") (pinfunction "PB6_136") (pintype "bidirectional"))
    )
    (net (code "63") (name "unconnected-(IC1-PB7-Pad137)") (class "Default")
      (node (ref "IC1") (pin "137") (pinfunction "PB7_137") (pintype "bidirectional"))
    )
    (net (code "64") (name "unconnected-(IC1-PB8-Pad139)") (class "Default")
      (node (ref "IC1") (pin "139") (pinfunction "PB8_139") (pintype "bidirectional"))
    )
    (net (code "65") (name "unconnected-(IC1-PB9-Pad140)") (class "Default")
      (node (ref "IC1") (pin "140") (pinfunction "PB9_140") (pintype "bidirectional"))
    )
    (net (code "66") (name "unconnected-(IC1-PB10-Pad69)") (class "Default")
      (node (ref "IC1") (pin "69") (pinfunction "PB10_69") (pintype "bidirectional"))
    )
    (net (code "67") (name "unconnected-(IC1-PB11-Pad70)") (class "Default")
      (node (ref "IC1") (pin "70") (pinfunction "PB11_70") (pintype "bidirectional"))
    )
    (net (code "68") (name "unconnected-(IC1-PB12-Pad73)") (class "Default")
      (node (ref "IC1") (pin "73") (pinfunction "PB12_73") (pintype "bidirectional"))
    )
    (net (code "69") (name "unconnected-(IC1-PB13-Pad74)") (class "Default")
      (node (ref "IC1") (pin "74") (pinfunction "PB13_74") (pintype "bidirectional"))
    )
    (net (code "70") (name "unconnected-(IC1-PB14-Pad75)") (class "Default")
      (node (ref "IC1") (pin "75") (pinfunction "PB14_75") (pintype "bidirectional"))
    )
    (net (code "71") (name "unconnected-(IC1-PB15-Pad76)") (class "Default")
      (node (ref "IC1") (pin "76") (pinfunction "PB15_76") (pintype "bidirectional"))
    )
    (net (code "72") (name "unconnected-(IC1-PBO-Pad46)") (class "Default")
      (node (ref "IC1") (pin "46") (pinfunction "PBO_46") (pintype "bidirectional"))
    )
    (net (code "73") (name "unconnected-(IC1-PC1-Pad27)") (class "Default")
      (node (ref "IC1") (pin "27") (pinfunction "PC1_27") (pintype "bidirectional"))
    )
    (net (code "74") (name "unconnected-(IC1-PC2-Pad28)") (class "Default")
      (node (ref "IC1") (pin "28") (pinfunction "PC2_28") (pintype "bidirectional"))
    )
    (net (code "75") (name "unconnected-(IC1-PC3-Pad29)") (class "Default")
      (node (ref "IC1") (pin "29") (pinfunction "PC3_29") (pintype "bidirectional"))
    )
    (net (code "76") (name "unconnected-(IC1-PC4-Pad44)") (class "Default")
      (node (ref "IC1") (pin "44") (pinfunction "PC4_44") (pintype "bidirectional"))
    )
    (net (code "77") (name "unconnected-(IC1-PC5-Pad45)") (class "Default")
      (node (ref "IC1") (pin "45") (pinfunction "PC5_45") (pintype "bidirectional"))
    )
    (net (code "78") (name "unconnected-(IC1-PC6-Pad96)") (class "Default")
      (node (ref "IC1") (pin "96") (pinfunction "PC6_96") (pintype "bidirectional"))
    )
    (net (code "79") (name "unconnected-(IC1-PC7-Pad97)") (class "Default")
      (node (ref "IC1") (pin "97") (pinfunction "PC7_97") (pintype "bidirectional"))
    )
    (net (code "80") (name "unconnected-(IC1-PC8-Pad98)") (class "Default")
      (node (ref "IC1") (pin "98") (pinfunction "PC8_98") (pintype "bidirectional"))
    )
    (net (code "81") (name "unconnected-(IC1-PC9-Pad99)") (class "Default")
      (node (ref "IC1") (pin "99") (pinfunction "PC9_99") (pintype "bidirectional"))
    )
    (net (code "82") (name "unconnected-(IC1-PC10-Pad111)") (class "Default")
      (node (ref "IC1") (pin "111") (pinfunction "PC10_111") (pintype "bidirectional"))
    )
    (net (code "83") (name "unconnected-(IC1-PC13-Pad7)") (class "Default")
      (node (ref "IC1") (pin "7") (pinfunction "PC13_7") (pintype "bidirectional"))
    )
    (net (code "84") (name "unconnected-(IC1-PCO-Pad26)") (class "Default")
      (node (ref "IC1") (pin "26") (pinfunction "PCO_26") (pintype "bidirectional"))
    )
    (net (code "85") (name "unconnected-(IC1-PD1-Pad115)") (class "Default")
      (node (ref "IC1") (pin "115") (pinfunction "PD1_115") (pintype "bidirectional"))
    )
    (net (code "86") (name "unconnected-(IC1-PD3-Pad117)") (class "Default")
      (node (ref "IC1") (pin "117") (pinfunction "PD3_117") (pintype "bidirectional"))
    )
    (net (code "87") (name "unconnected-(IC1-PD4-Pad118)") (class "Default")
      (node (ref "IC1") (pin "118") (pinfunction "PD4_118") (pintype "bidirectional"))
    )
    (net (code "88") (name "unconnected-(IC1-PD5-Pad119)") (class "Default")
      (node (ref "IC1") (pin "119") (pinfunction "PD5_119") (pintype "bidirectional"))
    )
    (net (code "89") (name "unconnected-(IC1-PD6-Pad122)") (class "Default")
      (node (ref "IC1") (pin "122") (pinfunction "PD6_122") (pintype "bidirectional"))
    )
    (net (code "90") (name "unconnected-(IC1-PD7-Pad123)") (class "Default")
      (node (ref "IC1") (pin "123") (pinfunction "PD7_123") (pintype "bidirectional"))
    )
    (net (code "91") (name "unconnected-(IC1-PD8-Pad77)") (class "Default")
      (node (ref "IC1") (pin "77") (pinfunction "PD8_77") (pintype "bidirectional"))
    )
    (net (code "92") (name "unconnected-(IC1-PD9-Pad78)") (class "Default")
      (node (ref "IC1") (pin "78") (pinfunction "PD9_78") (pintype "bidirectional"))
    )
    (net (code "93") (name "unconnected-(IC1-PD10-Pad79)") (class "Default")
      (node (ref "IC1") (pin "79") (pinfunction "PD10_79") (pintype "bidirectional"))
    )
    (net (code "94") (name "unconnected-(IC1-PD11-Pad80)") (class "Default")
      (node (ref "IC1") (pin "80") (pinfunction "PD11_80") (pintype "bidirectional"))
    )
    (net (code "95") (name "unconnected-(IC1-PD12-Pad81)") (class "Default")
      (node (ref "IC1") (pin "81") (pinfunction "PD12_81") (pintype "bidirectional"))
    )
    (net (code "96") (name "unconnected-(IC1-PD13-Pad82)") (class "Default")
      (node (ref "IC1") (pin "82") (pinfunction "PD13_82") (pintype "bidirectional"))
    )
    (net (code "97") (name "unconnected-(IC1-PD14-Pad85)") (class "Default")
      (node (ref "IC1") (pin "85") (pinfunction "PD14_85") (pintype "bidirectional"))
    )
    (net (code "98") (name "unconnected-(IC1-PD15-Pad86)") (class "Default")
      (node (ref "IC1") (pin "86") (pinfunction "PD15_86") (pintype "bidirectional"))
    )
    (net (code "99") (name "unconnected-(IC1-PDO-Pad114)") (class "Default")
      (node (ref "IC1") (pin "114") (pinfunction "PDO_114") (pintype "bidirectional"))
    )
    (net (code "100") (name "unconnected-(IC1-PDR_ON-Pad143)") (class "Default")
      (node (ref "IC1") (pin "143") (pinfunction "PDR_ON_143") (pintype "bidirectional"))
    )
    (net (code "101") (name "unconnected-(IC1-PE1-Pad142)") (class "Default")
      (node (ref "IC1") (pin "142") (pinfunction "PE1_142") (pintype "bidirectional"))
    )
    (net (code "102") (name "unconnected-(IC1-PE2-Pad1)") (class "Default")
      (node (ref "IC1") (pin "1") (pinfunction "PE2_1") (pintype "bidirectional"))
    )
    (net (code "103") (name "unconnected-(IC1-PE3-Pad2)") (class "Default")
      (node (ref "IC1") (pin "2") (pinfunction "PE3_2") (pintype "bidirectional"))
    )
    (net (code "104") (name "unconnected-(IC1-PE4-Pad3)") (class "Default")
      (node (ref "IC1") (pin "3") (pinfunction "PE4_3") (pintype "bidirectional"))
    )
    (net (code "105") (name "unconnected-(IC1-PE5-Pad4)") (class "Default")
      (node (ref "IC1") (pin "4") (pinfunction "PE5_4") (pintype "bidirectional"))
    )
    (net (code "106") (name "unconnected-(IC1-PE11-Pad64)") (class "Default")
      (node (ref "IC1") (pin "64") (pinfunction "PE11_64") (pintype "bidirectional"))
    )
    (net (code "107") (name "unconnected-(IC1-PE12-Pad65)") (class "Default")
      (node (ref "IC1") (pin "65") (pinfunction "PE12_65") (pintype "bidirectional"))
    )
    (net (code "108") (name "unconnected-(IC1-PE13-Pad66)") (class "Default")
      (node (ref "IC1") (pin "66") (pinfunction "PE13_66") (pintype "bidirectional"))
    )
    (net (code "109") (name "unconnected-(IC1-PE14-Pad67)") (class "Default")
      (node (ref "IC1") (pin "67") (pinfunction "PE14_67") (pintype "bidirectional"))
    )
    (net (code "110") (name "unconnected-(IC1-PE15-Pad68)") (class "Default")
      (node (ref "IC1") (pin "68") (pinfunction "PE15_68") (pintype "bidirectional"))
    )
    (net (code "111") (name "unconnected-(IC1-PEO-Pad141)") (class "Default")
      (node (ref "IC1") (pin "141") (pinfunction "PEO_141") (pintype "bidirectional"))
    )
    (net (code "112") (name "unconnected-(IC1-PF1-Pad11)") (class "Default")
      (node (ref "IC1") (pin "11") (pinfunction "PF1_11") (pintype "bidirectional"))
    )
    (net (code "113") (name "unconnected-(IC1-PF2-Pad12)") (class "Default")
      (node (ref "IC1") (pin "12") (pinfunction "PF2_12") (pintype "bidirectional"))
    )
    (net (code "114") (name "unconnected-(IC1-PF3-Pad13)") (class "Default")
      (node (ref "IC1") (pin "13") (pinfunction "PF3_13") (pintype "bidirectional"))
    )
    (net (code "115") (name "unconnected-(IC1-PF4-Pad14)") (class "Default")
      (node (ref "IC1") (pin "14") (pinfunction "PF4_14") (pintype "bidirectional"))
    )
    (net (code "116") (name "unconnected-(IC1-PF5-Pad15)") (class "Default")
      (node (ref "IC1") (pin "15") (pinfunction "PF5_15") (pintype "bidirectional"))
    )
    (net (code "117") (name "unconnected-(IC1-PF7-Pad19)") (class "Default")
      (node (ref "IC1") (pin "19") (pinfunction "PF7_19") (pintype "bidirectional"))
    )
    (net (code "118") (name "unconnected-(IC1-PF8-Pad20)") (class "Default")
      (node (ref "IC1") (pin "20") (pinfunction "PF8_20") (pintype "bidirectional"))
    )
    (net (code "119") (name "unconnected-(IC1-PF9-Pad21)") (class "Default")
      (node (ref "IC1") (pin "21") (pinfunction "PF9_21") (pintype "bidirectional"))
    )
    (net (code "120") (name "unconnected-(IC1-PF10-Pad22)") (class "Default")
      (node (ref "IC1") (pin "22") (pinfunction "PF10_22") (pintype "bidirectional"))
    )
    (net (code "121") (name "unconnected-(IC1-PF11-Pad49)") (class "Default")
      (node (ref "IC1") (pin "49") (pinfunction "PF11_49") (pintype "bidirectional"))
    )
    (net (code "122") (name "unconnected-(IC1-PF12-Pad50)") (class "Default")
      (node (ref "IC1") (pin "50") (pinfunction "PF12_50") (pintype "bidirectional"))
    )
    (net (code "123") (name "unconnected-(IC1-PF13-Pad53)") (class "Default")
      (node (ref "IC1") (pin "53") (pinfunction "PF13_53") (pintype "bidirectional"))
    )
    (net (code "124") (name "unconnected-(IC1-PF14-Pad54)") (class "Default")
      (node (ref "IC1") (pin "54") (pinfunction "PF14_54") (pintype "bidirectional"))
    )
    (net (code "125") (name "unconnected-(IC1-PF15-Pad55)") (class "Default")
      (node (ref "IC1") (pin "55") (pinfunction "PF15_55") (pintype "bidirectional"))
    )
    (net (code "126") (name "unconnected-(IC1-PFO-Pad10)") (class "Default")
      (node (ref "IC1") (pin "10") (pinfunction "PFO_10") (pintype "bidirectional"))
    )
    (net (code "127") (name "unconnected-(IC1-PG1-Pad57)") (class "Default")
      (node (ref "IC1") (pin "57") (pinfunction "PG1_57") (pintype "bidirectional"))
    )
    (net (code "128") (name "unconnected-(IC1-PG2-Pad87)") (class "Default")
      (node (ref "IC1") (pin "87") (pinfunction "PG2_87") (pintype "bidirectional"))
    )
    (net (code "129") (name "unconnected-(IC1-PG3-Pad88)") (class "Default")
      (node (ref "IC1") (pin "88") (pinfunction "PG3_88") (pintype "bidirectional"))
    )
    (net (code "130") (name "unconnected-(IC1-PG4-Pad89)") (class "Default")
      (node (ref "IC1") (pin "89") (pinfunction "PG4_89") (pintype "bidirectional"))
    )
    (net (code "131") (name "unconnected-(IC1-PG5-Pad90)") (class "Default")
      (node (ref "IC1") (pin "90") (pinfunction "PG5_90") (pintype "bidirectional"))
    )
    (net (code "132") (name "unconnected-(IC1-PG6-Pad91)") (class "Default")
      (node (ref "IC1") (pin "91") (pinfunction "PG6_91") (pintype "bidirectional"))
    )
    (net (code "133") (name "unconnected-(IC1-PG7-Pad92)") (class "Default")
      (node (ref "IC1") (pin "92") (pinfunction "PG7_92") (pintype "bidirectional"))
    )
    (net (code "134") (name "unconnected-(IC1-PG8-Pad93)") (class "Default")
      (node (ref "IC1") (pin "93") (pinfunction "PG8_93") (pintype "bidirectional"))
    )
    (net (code "135") (name "unconnected-(IC1-PG9-Pad124)") (class "Default")
      (node (ref "IC1") (pin "124") (pinfunction "PG9_124") (pintype "bidirectional"))
    )
    (net (code "136") (name "unconnected-(IC1-PG10-Pad125)") (class "Default")
      (node (ref "IC1") (pin "125") (pinfunction "PG10_125") (pintype "bidirectional"))
    )
    (net (code "137") (name "unconnected-(IC1-PG11-Pad126)") (class "Default")
      (node (ref "IC1") (pin "126") (pinfunction "PG11_126") (pintype "bidirectional"))
    )
    (net (code "138") (name "unconnected-(IC1-PG12-Pad127)") (class "Default")
      (node (ref "IC1") (pin "127") (pinfunction "PG12_127") (pintype "bidirectional"))
    )
    (net (code "139") (name "unconnected-(IC1-PG13-Pad128)") (class "Default")
      (node (ref "IC1") (pin "128") (pinfunction "PG13_128") (pintype "bidirectional"))
    )
    (net (code "140") (name "unconnected-(IC1-PG14-Pad129)") (class "Default")
      (node (ref "IC1") (pin "129") (pinfunction "PG14_129") (pintype "bidirectional"))
    )
    (net (code "141") (name "unconnected-(IC1-PG15-Pad132)") (class "Default")
      (node (ref "IC1") (pin "132") (pinfunction "PG15_132") (pintype "bidirectional"))
    )
    (net (code "142") (name "unconnected-(IC1-PGO-Pad56)") (class "Default")
      (node (ref "IC1") (pin "56") (pinfunction "PGO_56") (pintype "bidirectional"))
    )
    (net (code "143") (name "unconnected-(IC1-VBAT-Pad6)") (class "Default")
      (node (ref "IC1") (pin "6") (pinfunction "VBAT_6") (pintype "bidirectional"))
    )
    (net (code "144") (name "unconnected-(J2-NC{slash}TDI-Pad8)") (class "Default")
      (node (ref "J2") (pin "8") (pinfunction "NC/TDI_8") (pintype "bidirectional"))
    )
    (net (code "145") (name "unconnected-(LCDCONNECTORB-KL-Pad10)") (class "Default")
      (node (ref "LCDCONNECTOR") (pin "10") (pinfunction "KL_10") (pintype "passive"))
    )
    (net (code "146") (name "unconnected-(LCDCONNECTORE-KL-Pad13)") (class "Default")
      (node (ref "LCDCONNECTOR") (pin "13") (pinfunction "KL_13") (pintype "passive"))
    )
    (net (code "147") (name "unconnected-(LCDCONNECTORF-KL-Pad14)") (class "Default")
      (node (ref "LCDCONNECTOR") (pin "14") (pinfunction "KL_14") (pintype "passive"))
    )
    (net (code "148") (name "unconnected-(LCDCONNECTORG-KL-Pad15)") (class "Default")
      (node (ref "LCDCONNECTOR") (pin "15") (pinfunction "KL_15") (pintype "passive"))
    )
    (net (code "149") (name "unconnected-(LCDCONNECTORH-KL-Pad16)") (class "Default")
      (node (ref "LCDCONNECTOR") (pin "16") (pinfunction "KL_16") (pintype "passive"))
    )
    (net (code "150") (name "unconnected-(LCDCONNECTORR-KL-Pad7)") (class "Default")
      (node (ref "LCDCONNECTOR") (pin "7") (pinfunction "KL_7") (pintype "passive"))
    )
    (net (code "151") (name "unconnected-(LCDCONNECTORT-KL-Pad9)") (class "Default")
      (node (ref "LCDCONNECTOR") (pin "9") (pinfunction "KL_9") (pintype "passive"))
    )
    (net (code "152") (name "unconnected-(P1-Pad2)") (class "Default")
      (node (ref "P1") (pin "2") (pinfunction "2_2") (pintype "passive"))
    )
    (net (code "153") (name "unconnected-(P1-Pad3)") (class "Default")
      (node (ref "P1") (pin "3") (pinfunction "3_3") (pintype "passive"))
    )
    (net (code "154") (name "unconnected-(P1-Pad4)") (class "Default")
      (node (ref "P1") (pin "4") (pinfunction "4_4") (pintype "passive"))
    )
    (net (code "155") (name "unconnected-(P1-Pad5)") (class "Default")
      (node (ref "P1") (pin "5") (pinfunction "5_5") (pintype "passive"))
    )
    (net (code "156") (name "unconnected-(P1-Pad6)") (class "Default")
      (node (ref "P1") (pin "6") (pinfunction "6_6") (pintype "passive"))
    )
    (net (code "157") (name "unconnected-(P1-Pad9)") (class "Default")
      (node (ref "P1") (pin "9") (pinfunction "9_9") (pintype "passive"))
    )
    (net (code "158") (name "unconnected-(P1-Pad10)") (class "Default")
      (node (ref "P1") (pin "10") (pinfunction "10_10") (pintype "passive"))
    )
    (net (code "159") (name "unconnected-(P1-Pad11)") (class "Default")
      (node (ref "P1") (pin "11") (pinfunction "11_11") (pintype "passive"))
    )
    (net (code "160") (name "unconnected-(P1-Pad12)") (class "Default")
      (node (ref "P1") (pin "12") (pinfunction "12_12") (pintype "passive"))
    )
    (net (code "161") (name "unconnected-(P1-Pad15)") (class "Default")
      (node (ref "P1") (pin "15") (pinfunction "15_15") (pintype "passive"))
    )
    (net (code "162") (name "unconnected-(P1-Pad16)") (class "Default")
      (node (ref "P1") (pin "16") (pinfunction "16_16") (pintype "passive"))
    )
    (net (code "163") (name "unconnected-(P1-Pad17)") (class "Default")
      (node (ref "P1") (pin "17") (pinfunction "17_17") (pintype "passive"))
    )
    (net (code "164") (name "unconnected-(P1-Pad18)") (class "Default")
      (node (ref "P1") (pin "18") (pinfunction "18_18") (pintype "passive"))
    )
    (net (code "165") (name "unconnected-(P1-Pad21)") (class "Default")
      (node (ref "P1") (pin "21") (pinfunction "21_21") (pintype "passive"))
    )
    (net (code "166") (name "unconnected-(P1-Pad22)") (class "Default")
      (node (ref "P1") (pin "22") (pinfunction "22_22") (pintype "passive"))
    )
    (net (code "167") (name "unconnected-(P1-Pad23)") (class "Default")
      (node (ref "P1") (pin "23") (pinfunction "23_23") (pintype "passive"))
    )
    (net (code "168") (name "unconnected-(P1-Pad24)") (class "Default")
      (node (ref "P1") (pin "24") (pinfunction "24_24") (pintype "passive"))
    )
    (net (code "169") (name "unconnected-(P1-Pad27)") (class "Default")
      (node (ref "P1") (pin "27") (pinfunction "27_27") (pintype "passive"))
    )
    (net (code "170") (name "unconnected-(P1-Pad28)") (class "Default")
      (node (ref "P1") (pin "28") (pinfunction "28_28") (pintype "passive"))
    )
    (net (code "171") (name "unconnected-(P1-Pad29)") (class "Default")
      (node (ref "P1") (pin "29") (pinfunction "29_29") (pintype "passive"))
    )
    (net (code "172") (name "unconnected-(P1-Pad30)") (class "Default")
      (node (ref "P1") (pin "30") (pinfunction "30_30") (pintype "passive"))
    )
    (net (code "173") (name "unconnected-(P1-Pad33)") (class "Default")
      (node (ref "P1") (pin "33") (pinfunction "33_33") (pintype "passive"))
    )
    (net (code "174") (name "unconnected-(P1-Pad34)") (class "Default")
      (node (ref "P1") (pin "34") (pinfunction "34_34") (pintype "passive"))
    )
    (net (code "175") (name "unconnected-(P1-Pad35)") (class "Default")
      (node (ref "P1") (pin "35") (pinfunction "35_35") (pintype "passive"))
    )
    (net (code "176") (name "unconnected-(P1-Pad36)") (class "Default")
      (node (ref "P1") (pin "36") (pinfunction "36_36") (pintype "passive"))
    )
    (net (code "177") (name "unconnected-(P1-Pad39)") (class "Default")
      (node (ref "P1") (pin "39") (pinfunction "39_39") (pintype "passive"))
    )
    (net (code "178") (name "unconnected-(P1-Pad40)") (class "Default")
      (node (ref "P1") (pin "40") (pinfunction "40_40") (pintype "passive"))
    )
    (net (code "179") (name "unconnected-(P1-Pad41)") (class "Default")
      (node (ref "P1") (pin "41") (pinfunction "41_41") (pintype "passive"))
    )
    (net (code "180") (name "unconnected-(P1-Pad42)") (class "Default")
      (node (ref "P1") (pin "42") (pinfunction "42_42") (pintype "passive"))
    )
    (net (code "181") (name "unconnected-(P1-Pad45)") (class "Default")
      (node (ref "P1") (pin "45") (pinfunction "45_45") (pintype "passive"))
    )
    (net (code "182") (name "unconnected-(P1-Pad46)") (class "Default")
      (node (ref "P1") (pin "46") (pinfunction "46_46") (pintype "passive"))
    )
    (net (code "183") (name "unconnected-(P1-Pad47)") (class "Default")
      (node (ref "P1") (pin "47") (pinfunction "47_47") (pintype "passive"))
    )
    (net (code "184") (name "unconnected-(P1-Pad48)") (class "Default")
      (node (ref "P1") (pin "48") (pinfunction "48_48") (pintype "passive"))
    )
    (net (code "185") (name "unconnected-(P1-Pad52)") (class "Default")
      (node (ref "P1") (pin "52") (pinfunction "52_52") (pintype "passive"))
    )
    (net (code "186") (name "unconnected-(P1-Pad54)") (class "Default")
      (node (ref "P1") (pin "54") (pinfunction "54_54") (pintype "passive"))
    )
    (net (code "187") (name "unconnected-(P1-Pad57)") (class "Default")
      (node (ref "P1") (pin "57") (pinfunction "57_57") (pintype "passive"))
    )
    (net (code "188") (name "unconnected-(P1-Pad58)") (class "Default")
      (node (ref "P1") (pin "58") (pinfunction "58_58") (pintype "passive"))
    )
    (net (code "189") (name "unconnected-(P1-Pad59)") (class "Default")
      (node (ref "P1") (pin "59") (pinfunction "59_59") (pintype "passive"))
    )
    (net (code "190") (name "unconnected-(P1-Pad60)") (class "Default")
      (node (ref "P1") (pin "60") (pinfunction "60_60") (pintype "passive"))
    )
    (net (code "191") (name "unconnected-(P1-Pad63)") (class "Default")
      (node (ref "P1") (pin "63") (pinfunction "63_63") (pintype "passive"))
    )
    (net (code "192") (name "unconnected-(P1-Pad64)") (class "Default")
      (node (ref "P1") (pin "64") (pinfunction "64_64") (pintype "passive"))
    )
    (net (code "193") (name "unconnected-(P1-Pad65)") (class "Default")
      (node (ref "P1") (pin "65") (pinfunction "65_65") (pintype "passive"))
    )
    (net (code "194") (name "unconnected-(P1-Pad66)") (class "Default")
      (node (ref "P1") (pin "66") (pinfunction "66_66") (pintype "passive"))
    )
    (net (code "195") (name "unconnected-(P1-Pad69)") (class "Default")
      (node (ref "P1") (pin "69") (pinfunction "69_69") (pintype "passive"))
    )
    (net (code "196") (name "unconnected-(P1-Pad70)") (class "Default")
      (node (ref "P1") (pin "70") (pinfunction "70_70") (pintype "passive"))
    )
    (net (code "197") (name "unconnected-(P1-Pad71)") (class "Default")
      (node (ref "P1") (pin "71") (pinfunction "71_71") (pintype "passive"))
    )
    (net (code "198") (name "unconnected-(P1-Pad72)") (class "Default")
      (node (ref "P1") (pin "72") (pinfunction "72_72") (pintype "passive"))
    )
    (net (code "199") (name "unconnected-(P1-Pad75)") (class "Default")
      (node (ref "P1") (pin "75") (pinfunction "75_75") (pintype "passive"))
    )
    (net (code "200") (name "unconnected-(P1-Pad76)") (class "Default")
      (node (ref "P1") (pin "76") (pinfunction "76_76") (pintype "passive"))
    )
    (net (code "201") (name "unconnected-(P1-Pad77)") (class "Default")
      (node (ref "P1") (pin "77") (pinfunction "77_77") (pintype "passive"))
    )
    (net (code "202") (name "unconnected-(P1-Pad78)") (class "Default")
      (node (ref "P1") (pin "78") (pinfunction "78_78") (pintype "passive"))
    )
    (net (code "203") (name "unconnected-(P1-Pad81)") (class "Default")
      (node (ref "P1") (pin "81") (pinfunction "81_81") (pintype "passive"))
    )
    (net (code "204") (name "unconnected-(P1-Pad82)") (class "Default")
      (node (ref "P1") (pin "82") (pinfunction "82_82") (pintype "passive"))
    )
    (net (code "205") (name "unconnected-(P1-Pad83)") (class "Default")
      (node (ref "P1") (pin "83") (pinfunction "83_83") (pintype "passive"))
    )
    (net (code "206") (name "unconnected-(P1-Pad84)") (class "Default")
      (node (ref "P1") (pin "84") (pinfunction "84_84") (pintype "passive"))
    )
    (net (code "207") (name "unconnected-(P1-Pad87)") (class "Default")
      (node (ref "P1") (pin "87") (pinfunction "87_87") (pintype "passive"))
    )
    (net (code "208") (name "unconnected-(P1-Pad88)") (class "Default")
      (node (ref "P1") (pin "88") (pinfunction "88_88") (pintype "passive"))
    )
    (net (code "209") (name "unconnected-(P1-Pad89)") (class "Default")
      (node (ref "P1") (pin "89") (pinfunction "89_89") (pintype "passive"))
    )
    (net (code "210") (name "unconnected-(P1-Pad90)") (class "Default")
      (node (ref "P1") (pin "90") (pinfunction "90_90") (pintype "passive"))
    )
    (net (code "211") (name "unconnected-(P1-Pad93)") (class "Default")
      (node (ref "P1") (pin "93") (pinfunction "93_93") (pintype "passive"))
    )
    (net (code "212") (name "unconnected-(P1-Pad94)") (class "Default")
      (node (ref "P1") (pin "94") (pinfunction "94_94") (pintype "passive"))
    )
    (net (code "213") (name "unconnected-(P1-Pad95)") (class "Default")
      (node (ref "P1") (pin "95") (pinfunction "95_95") (pintype "passive"))
    )
    (net (code "214") (name "unconnected-(P1-Pad96)") (class "Default")
      (node (ref "P1") (pin "96") (pinfunction "96_96") (pintype "passive"))
    )
    (net (code "215") (name "unconnected-(P1-Pad99)") (class "Default")
      (node (ref "P1") (pin "99") (pinfunction "99_99") (pintype "passive"))
    )
    (net (code "216") (name "unconnected-(P1-Pad100)") (class "Default")
      (node (ref "P1") (pin "100") (pinfunction "100_100") (pintype "passive"))
    )
    (net (code "217") (name "unconnected-(P1-Pad101)") (class "Default")
      (node (ref "P1") (pin "101") (pinfunction "101_101") (pintype "passive"))
    )
    (net (code "218") (name "unconnected-(P1-Pad102)") (class "Default")
      (node (ref "P1") (pin "102") (pinfunction "102_102") (pintype "passive"))
    )
    (net (code "219") (name "unconnected-(P1-Pad105)") (class "Default")
      (node (ref "P1") (pin "105") (pinfunction "105_105") (pintype "passive"))
    )
    (net (code "220") (name "unconnected-(P1-Pad106)") (class "Default")
      (node (ref "P1") (pin "106") (pinfunction "106_106") (pintype "passive"))
    )
    (net (code "221") (name "unconnected-(P1-Pad107)") (class "Default")
      (node (ref "P1") (pin "107") (pinfunction "107_107") (pintype "passive"))
    )
    (net (code "222") (name "unconnected-(P1-Pad108)") (class "Default")
      (node (ref "P1") (pin "108") (pinfunction "108_108") (pintype "passive"))
    )
    (net (code "223") (name "unconnected-(P1-Pad111)") (class "Default")
      (node (ref "P1") (pin "111") (pinfunction "111_111") (pintype "passive"))
    )
    (net (code "224") (name "unconnected-(P1-Pad112)") (class "Default")
      (node (ref "P1") (pin "112") (pinfunction "112_112") (pintype "passive"))
    )
    (net (code "225") (name "unconnected-(P1-Pad113)") (class "Default")
      (node (ref "P1") (pin "113") (pinfunction "113_113") (pintype "passive"))
    )
    (net (code "226") (name "unconnected-(P1-Pad114)") (class "Default")
      (node (ref "P1") (pin "114") (pinfunction "114_114") (pintype "passive"))
    )
    (net (code "227") (name "unconnected-(P1-Pad117)") (class "Default")
      (node (ref "P1") (pin "117") (pinfunction "117_117") (pintype "passive"))
    )
    (net (code "228") (name "unconnected-(P1-Pad118)") (class "Default")
      (node (ref "P1") (pin "118") (pinfunction "118_118") (pintype "passive"))
    )
    (net (code "229") (name "unconnected-(P1-Pad119)") (class "Default")
      (node (ref "P1") (pin "119") (pinfunction "119_119") (pintype "passive"))
    )
    (net (code "230") (name "unconnected-(P1-Pad120)") (class "Default")
      (node (ref "P1") (pin "120") (pinfunction "120_120") (pintype "passive"))
    )
    (net (code "231") (name "unconnected-(P1-Pad123)") (class "Default")
      (node (ref "P1") (pin "123") (pinfunction "123_123") (pintype "passive"))
    )
    (net (code "232") (name "unconnected-(P1-Pad124)") (class "Default")
      (node (ref "P1") (pin "124") (pinfunction "124_124") (pintype "passive"))
    )
    (net (code "233") (name "unconnected-(P1-Pad125)") (class "Default")
      (node (ref "P1") (pin "125") (pinfunction "125_125") (pintype "passive"))
    )
    (net (code "234") (name "unconnected-(P1-Pad126)") (class "Default")
      (node (ref "P1") (pin "126") (pinfunction "126_126") (pintype "passive"))
    )
    (net (code "235") (name "unconnected-(P1-Pad128)") (class "Default")
      (node (ref "P1") (pin "128") (pinfunction "128_128") (pintype "passive"))
    )
    (net (code "236") (name "unconnected-(P1-Pad129)") (class "Default")
      (node (ref "P1") (pin "129") (pinfunction "129_129") (pintype "passive"))
    )
    (net (code "237") (name "unconnected-(P1-Pad130)") (class "Default")
      (node (ref "P1") (pin "130") (pinfunction "130_130") (pintype "passive"))
    )
    (net (code "238") (name "unconnected-(P1-Pad131)") (class "Default")
      (node (ref "P1") (pin "131") (pinfunction "131_131") (pintype "passive"))
    )
    (net (code "239") (name "unconnected-(P1-Pad132)") (class "Default")
      (node (ref "P1") (pin "132") (pinfunction "132_132") (pintype "passive"))
    )
    (net (code "240") (name "unconnected-(P1-Pad135)") (class "Default")
      (node (ref "P1") (pin "135") (pinfunction "135_135") (pintype "passive"))
    )
    (net (code "241") (name "unconnected-(P1-Pad136)") (class "Default")
      (node (ref "P1") (pin "136") (pinfunction "136_136") (pintype "passive"))
    )
    (net (code "242") (name "unconnected-(P1-Pad137)") (class "Default")
      (node (ref "P1") (pin "137") (pinfunction "137_137") (pintype "passive"))
    )
    (net (code "243") (name "unconnected-(P1-Pad138)") (class "Default")
      (node (ref "P1") (pin "138") (pinfunction "138_138") (pintype "passive"))
    )
    (net (code "244") (name "unconnected-(P1-Pad141)") (class "Default")
      (node (ref "P1") (pin "141") (pinfunction "141_141") (pintype "passive"))
    )
    (net (code "245") (name "unconnected-(P1-Pad142)") (class "Default")
      (node (ref "P1") (pin "142") (pinfunction "142_142") (pintype "passive"))
    )
    (net (code "246") (name "unconnected-(P1-Pad143)") (class "Default")
      (node (ref "P1") (pin "143") (pinfunction "143_143") (pintype "passive"))
    )
    (net (code "247") (name "unconnected-(P1-Pad144)") (class "Default")
      (node (ref "P1") (pin "144") (pinfunction "144_144") (pintype "passive"))
    )
    (net (code "248") (name "unconnected-(P1-Pad147)") (class "Default")
      (node (ref "P1") (pin "147") (pinfunction "147_147") (pintype "passive"))
    )
    (net (code "249") (name "unconnected-(P1-Pad148)") (class "Default")
      (node (ref "P1") (pin "148") (pinfunction "148_148") (pintype "passive"))
    )
    (net (code "250") (name "unconnected-(P1-Pad149)") (class "Default")
      (node (ref "P1") (pin "149") (pinfunction "149_149") (pintype "passive"))
    )
    (net (code "251") (name "unconnected-(P1-Pad150)") (class "Default")
      (node (ref "P1") (pin "150") (pinfunction "150_150") (pintype "passive"))
    )
    (net (code "252") (name "unconnected-(P1-Pad153)") (class "Default")
      (node (ref "P1") (pin "153") (pinfunction "153_153") (pintype "passive"))
    )
    (net (code "253") (name "unconnected-(P1-Pad154)") (class "Default")
      (node (ref "P1") (pin "154") (pinfunction "154_154") (pintype "passive"))
    )
    (net (code "254") (name "unconnected-(P1-Pad155)") (class "Default")
      (node (ref "P1") (pin "155") (pinfunction "155_155") (pintype "passive"))
    )
    (net (code "255") (name "unconnected-(P1-Pad156)") (class "Default")
      (node (ref "P1") (pin "156") (pinfunction "156_156") (pintype "passive"))
    )
    (net (code "256") (name "unconnected-(P1-Pad158)") (class "Default")
      (node (ref "P1") (pin "158") (pinfunction "158_158") (pintype "passive"))
    )
    (net (code "257") (name "unconnected-(P1-Pad159)") (class "Default")
      (node (ref "P1") (pin "159") (pinfunction "159_159") (pintype "passive"))
    )
    (net (code "258") (name "unconnected-(P1-Pad160)") (class "Default")
      (node (ref "P1") (pin "160") (pinfunction "160_160") (pintype "passive"))
    )
    (net (code "259") (name "unconnected-(P1-Pad161)") (class "Default")
      (node (ref "P1") (pin "161") (pinfunction "161_161") (pintype "passive"))
    )
    (net (code "260") (name "unconnected-(P1-Pad162)") (class "Default")
      (node (ref "P1") (pin "162") (pinfunction "162_162") (pintype "passive"))
    )
    (net (code "261") (name "unconnected-(P1-Pad166)") (class "Default")
      (node (ref "P1") (pin "166") (pinfunction "166_166") (pintype "passive"))
    )
    (net (code "262") (name "unconnected-(P1-Pad171)") (class "Default")
      (node (ref "P1") (pin "171") (pinfunction "171_171") (pintype "passive"))
    )
    (net (code "263") (name "unconnected-(P1-Pad172)") (class "Default")
      (node (ref "P1") (pin "172") (pinfunction "172_172") (pintype "passive"))
    )
    (net (code "264") (name "unconnected-(P1-Pad173)") (class "Default")
      (node (ref "P1") (pin "173") (pinfunction "173_173") (pintype "passive"))
    )
    (net (code "265") (name "unconnected-(P1-Pad174)") (class "Default")
      (node (ref "P1") (pin "174") (pinfunction "174_174") (pintype "passive"))
    )
    (net (code "266") (name "unconnected-(P1-Pad175)") (class "Default")
      (node (ref "P1") (pin "175") (pinfunction "175_175") (pintype "passive"))
    )
    (net (code "267") (name "unconnected-(P1-Pad176)") (class "Default")
      (node (ref "P1") (pin "176") (pinfunction "176_176") (pintype "passive"))
    )
    (net (code "268") (name "unconnected-(P1-Pad178)") (class "Default")
      (node (ref "P1") (pin "178") (pinfunction "178_178") (pintype "passive"))
    )
    (net (code "269") (name "unconnected-(P1-Pad179)") (class "Default")
      (node (ref "P1") (pin "179") (pinfunction "179_179") (pintype "passive"))
    )
    (net (code "270") (name "unconnected-(P1-Pad180)") (class "Default")
      (node (ref "P1") (pin "180") (pinfunction "180_180") (pintype "passive"))
    )
    (net (code "271") (name "unconnected-(P1-Pad189)") (class "Default")
      (node (ref "P1") (pin "189") (pinfunction "189_189") (pintype "passive"))
    )
    (net (code "272") (name "unconnected-(P1-Pad190)") (class "Default")
      (node (ref "P1") (pin "190") (pinfunction "190_190") (pintype "passive"))
    )
    (net (code "273") (name "unconnected-(PROXIMITYSENSOR-Pad4)") (class "Default")
      (node (ref "PROXIMITYSENSOR") (pin "4") (pinfunction "4_4") (pintype "passive"))
    )
    (net (code "274") (name "unconnected-(U1B-NC-Pad19)") (class "Default")
      (node (ref "U1") (pin "19") (pinfunction "NC_19") (pintype "passive"))
    )
    (net (code "275") (name "unconnected-(U1B-NC_2-Pad1)") (class "Default")
      (node (ref "U1") (pin "1") (pinfunction "NC_2_1") (pintype "passive"))
    )
    (net (code "276") (name "unconnected-(U1B-NC_3-Pad2)") (class "Default")
      (node (ref "U1") (pin "2") (pinfunction "NC_3_2") (pintype "passive"))
    )
    (net (code "277") (name "unconnected-(U1B-NC_4-Pad3)") (class "Default")
      (node (ref "U1") (pin "3") (pinfunction "NC_4_3") (pintype "passive"))
    )
    (net (code "278") (name "unconnected-(U1B-NC_5-Pad5)") (class "Default")
      (node (ref "U1") (pin "5") (pinfunction "NC_5_5") (pintype "passive"))
    )
    (net (code "279") (name "unconnected-(U1B-NC_6-Pad7)") (class "Default")
      (node (ref "U1") (pin "7") (pinfunction "NC_6_7") (pintype "passive"))
    )
    (net (code "280") (name "unconnected-(U1B-NC_7-Pad9)") (class "Default")
      (node (ref "U1") (pin "9") (pinfunction "NC_7_9") (pintype "passive"))
    )
    (net (code "281") (name "unconnected-(U1B-NC_8-Pad10)") (class "Default")
      (node (ref "U1") (pin "10") (pinfunction "NC_8_10") (pintype "passive"))
    )
    (net (code "282") (name "unconnected-(U1B-NC_9-Pad11)") (class "Default")
      (node (ref "U1") (pin "11") (pinfunction "NC_9_11") (pintype "passive"))
    )
    (net (code "283") (name "unconnected-(U1B-NC_10-Pad12)") (class "Default")
      (node (ref "U1") (pin "12") (pinfunction "NC_10_12") (pintype "passive"))
    )
    (net (code "284") (name "unconnected-(U1B-NC_11-Pad13)") (class "Default")
      (node (ref "U1") (pin "13") (pinfunction "NC_11_13") (pintype "passive"))
    )
    (net (code "285") (name "unconnected-(U1B-NC_12-Pad14)") (class "Default")
      (node (ref "U1") (pin "14") (pinfunction "NC_12_14") (pintype "passive"))
    )
    (net (code "286") (name "unconnected-(U1B-NC_13-Pad15)") (class "Default")
      (node (ref "U1") (pin "15") (pinfunction "NC_13_15") (pintype "passive"))
    )
    (net (code "287") (name "unconnected-(U1B-NC_14-Pad16)") (class "Default")
      (node (ref "U1") (pin "16") (pinfunction "NC_14_16") (pintype "passive"))
    )
    (net (code "288") (name "unconnected-(U1B-NC_15-Pad17)") (class "Default")
      (node (ref "U1") (pin "17") (pinfunction "NC_15_17") (pintype "passive"))
    )
    (net (code "289") (name "unconnected-(U1B-NC_16-Pad18)") (class "Default")
      (node (ref "U1") (pin "18") (pinfunction "NC_16_18") (pintype "passive"))
    )
  )
)
